# OBCv4_24.net
KiCad netlist of a schematic drawn in EAGLE
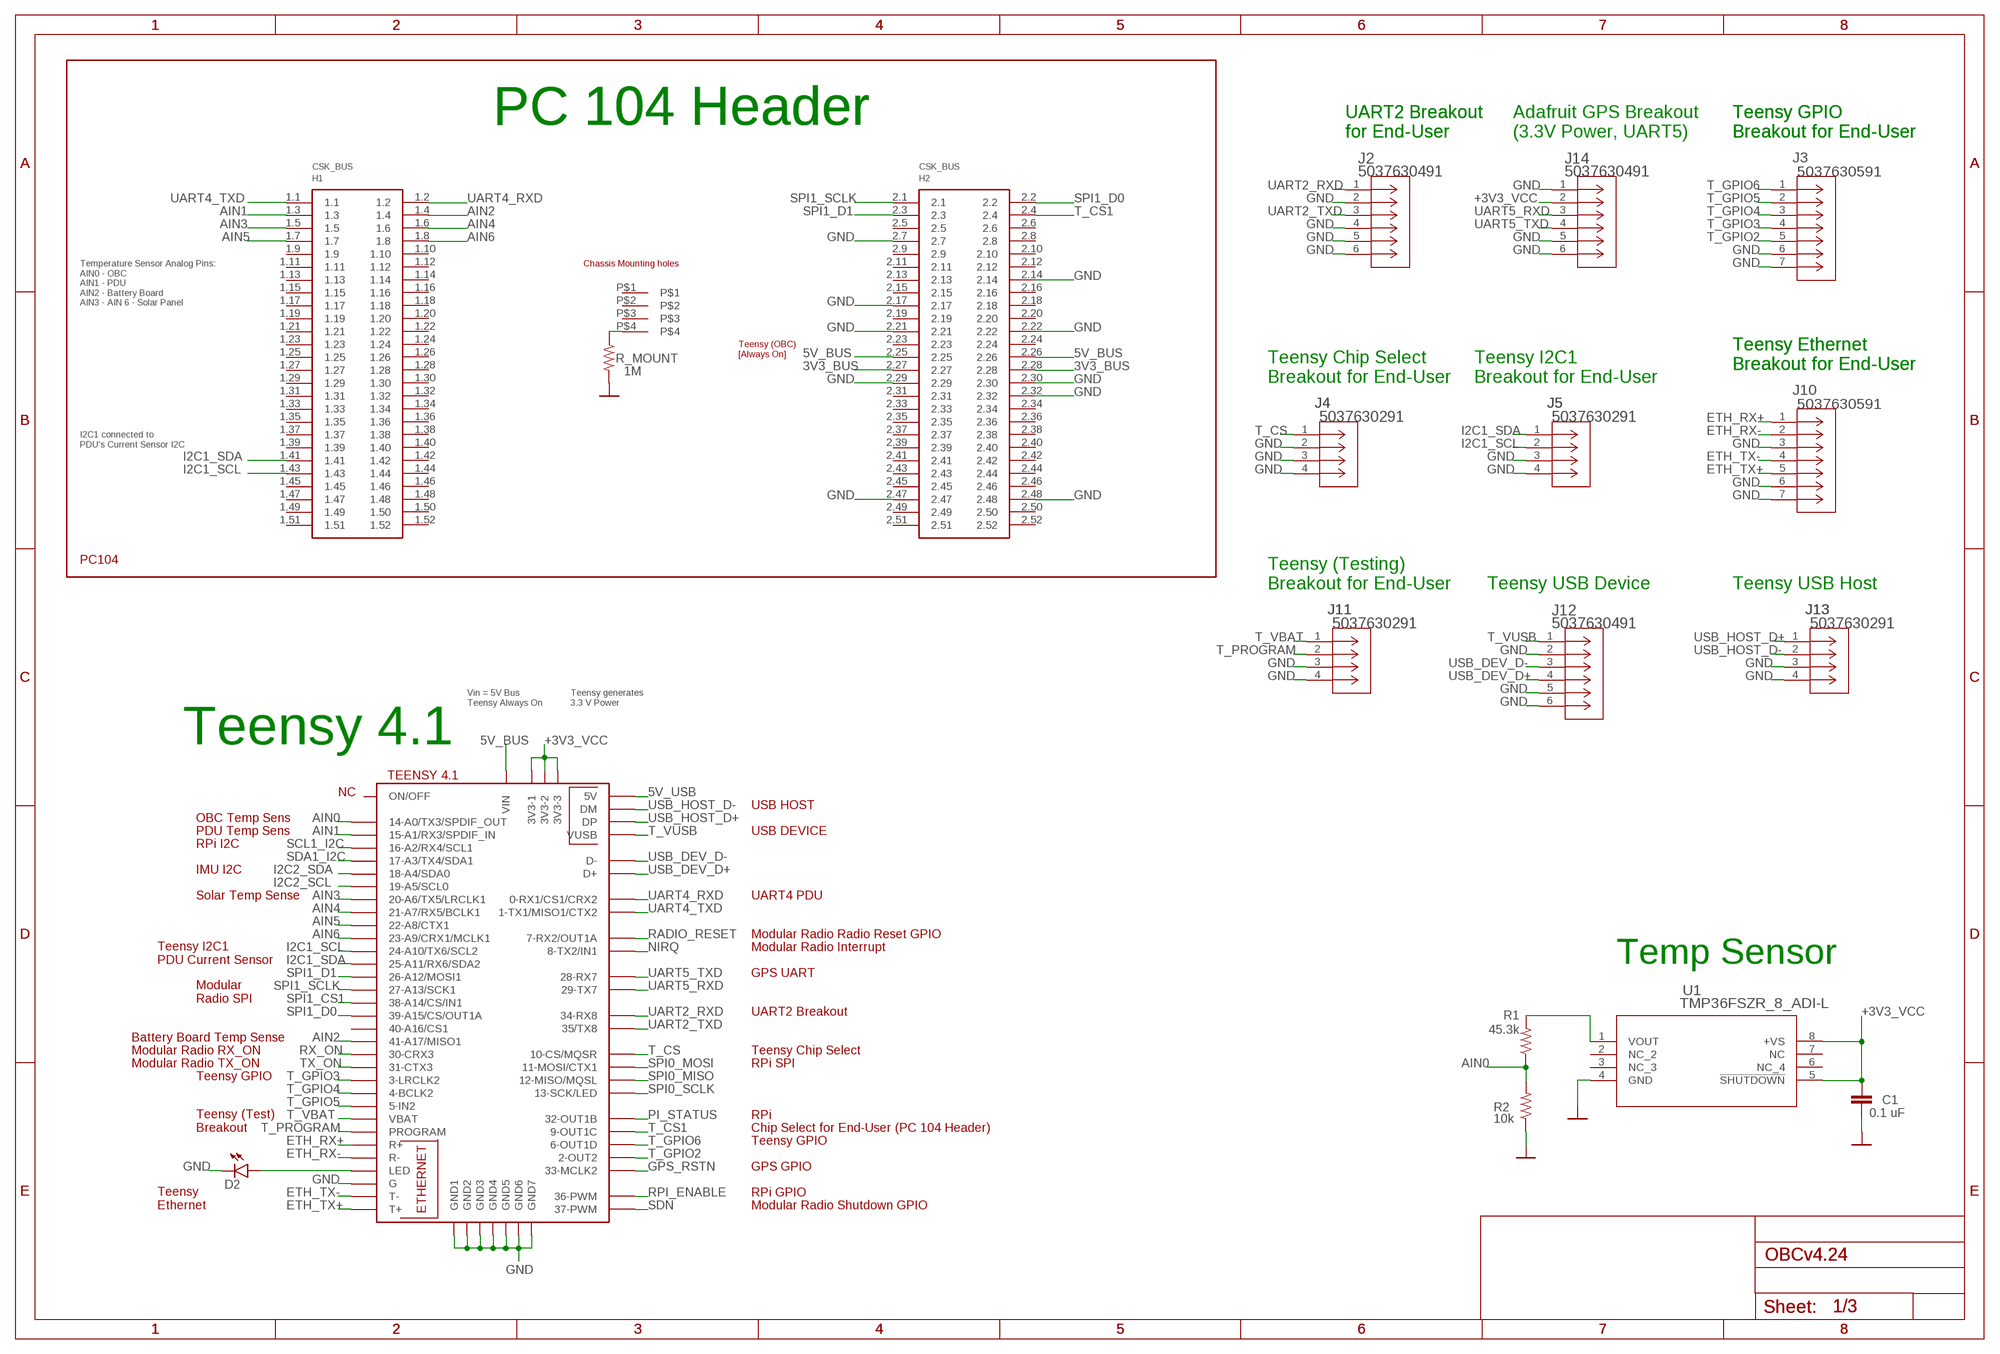
[diagram p0: schematic, sheet 1]
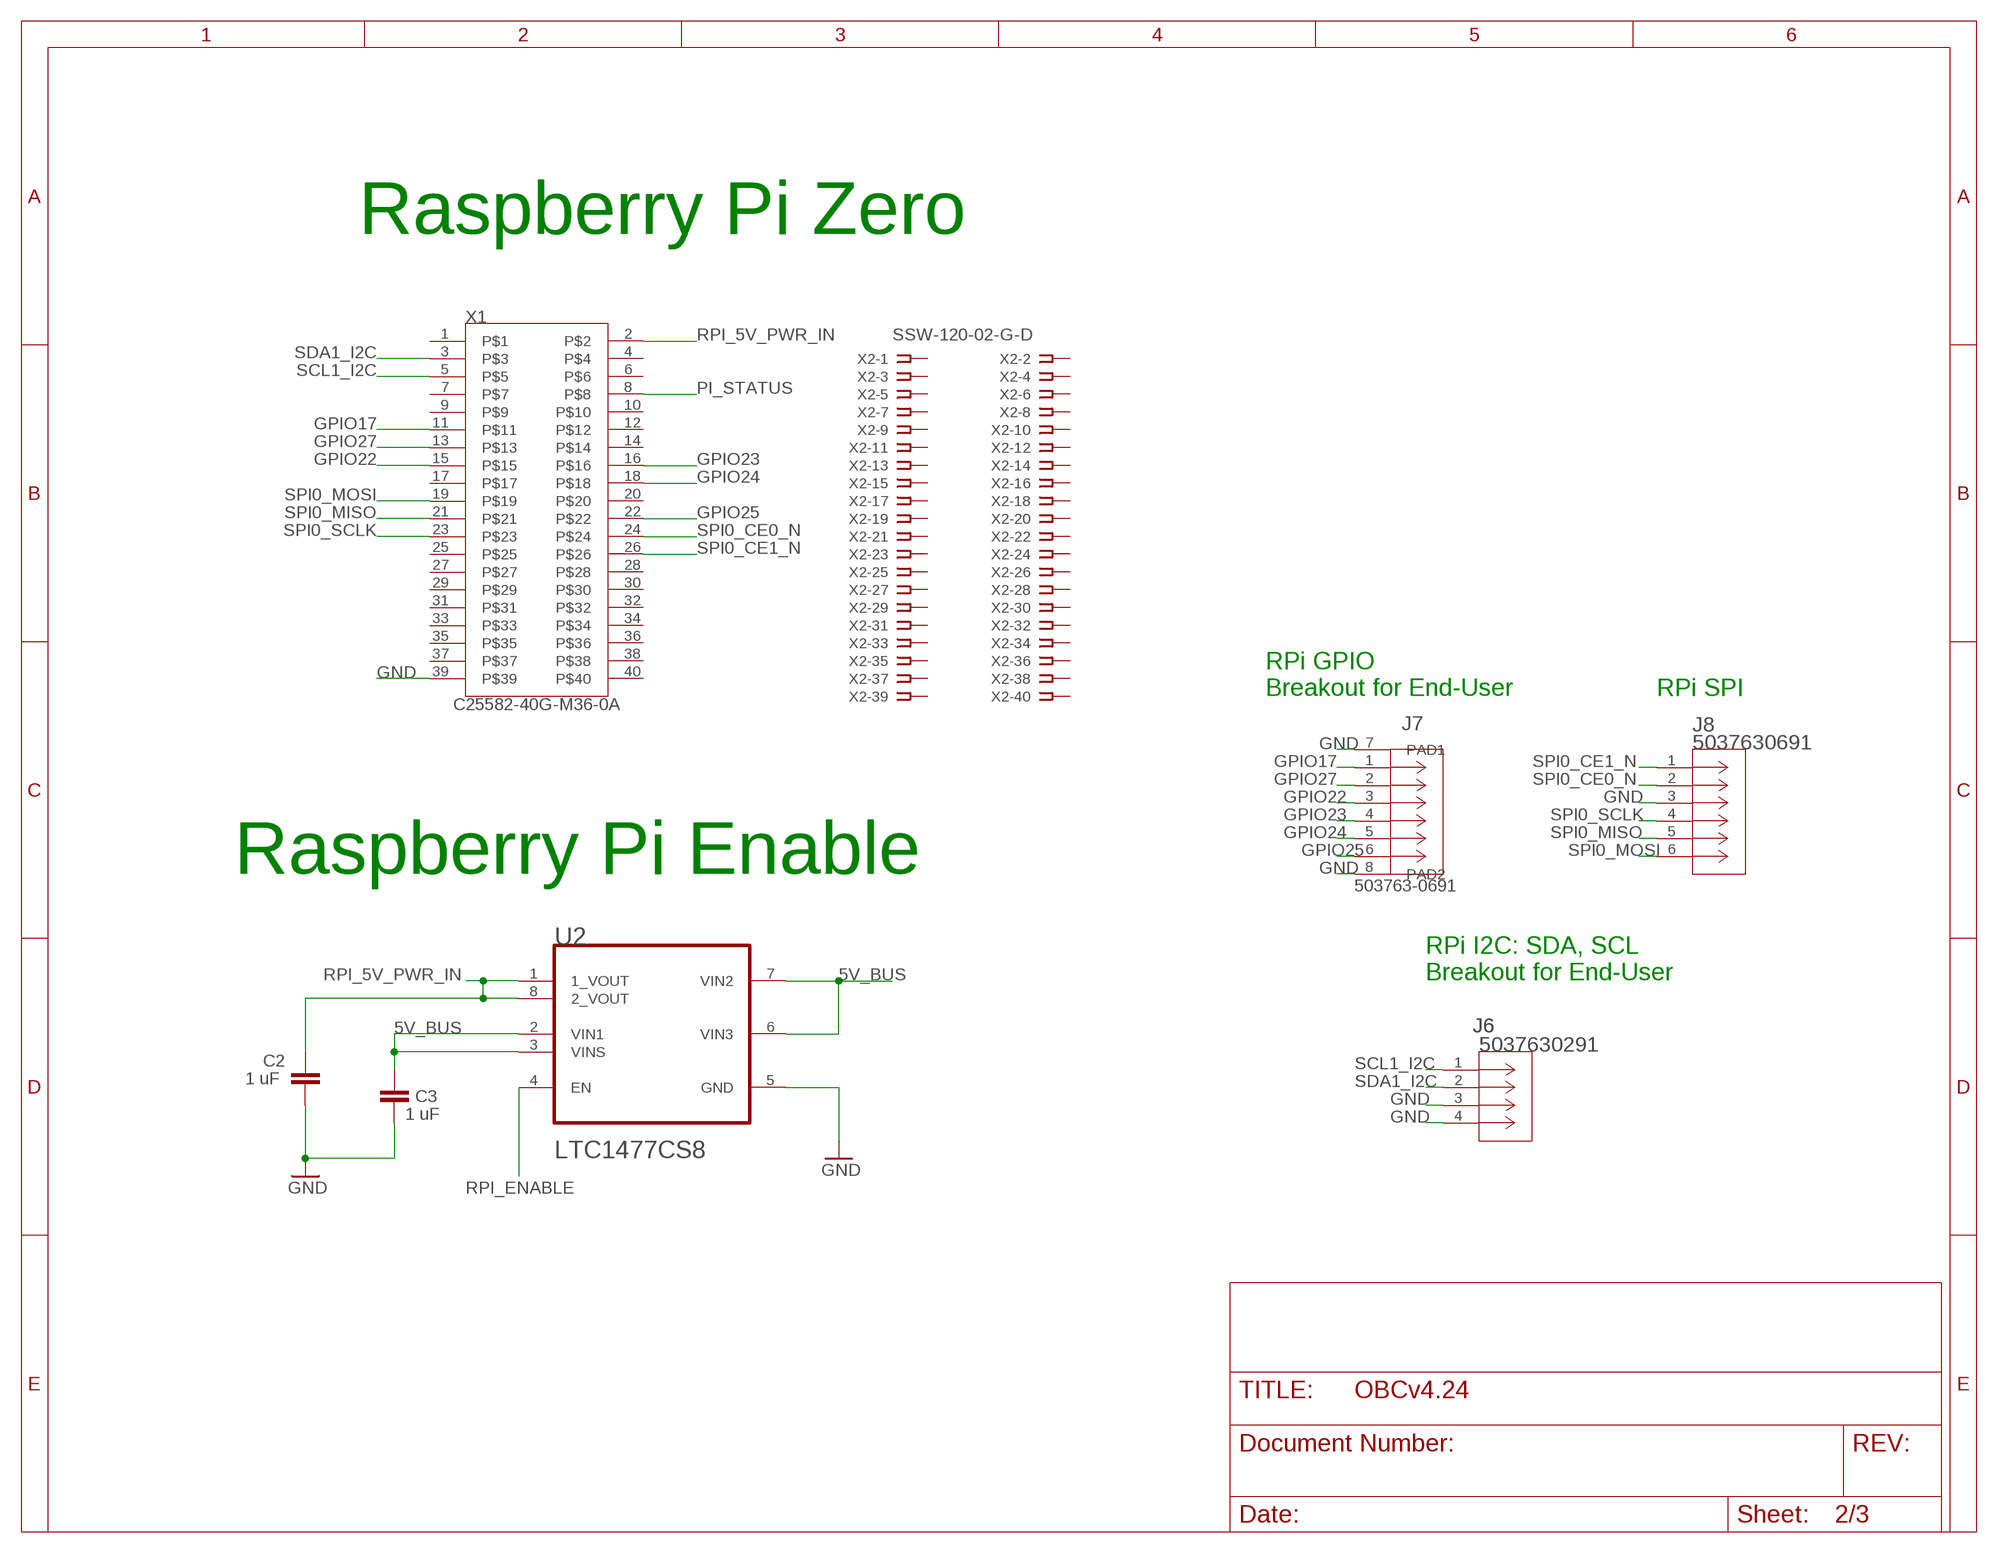
[diagram p1: schematic, sheet 2]
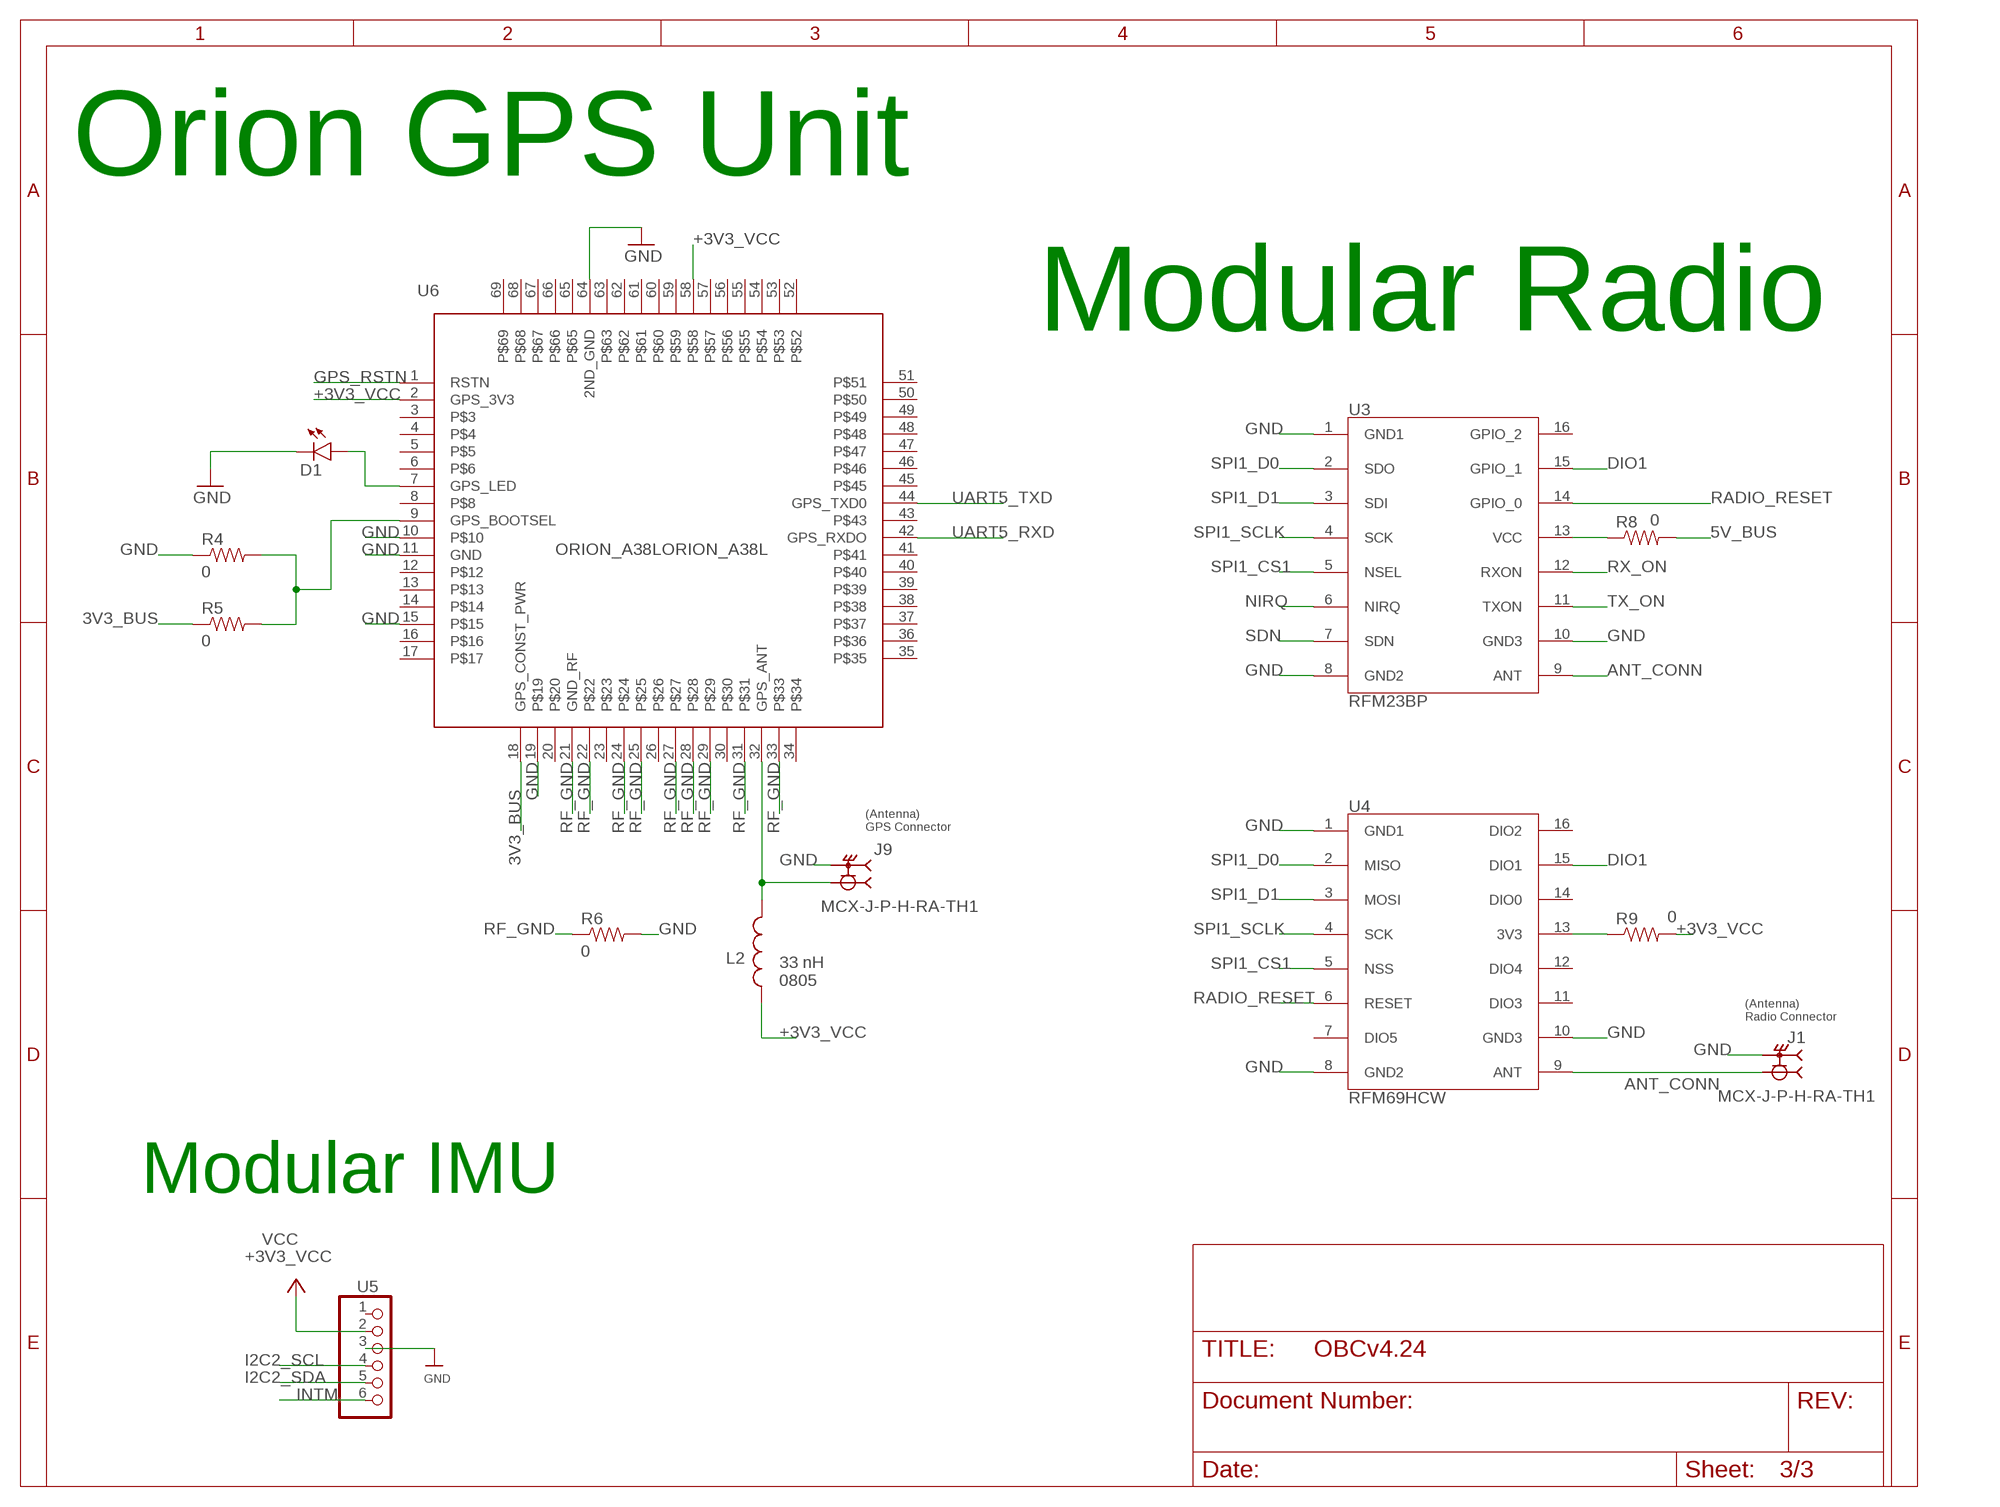
[diagram p2: schematic, sheet 3]

(export (version "E")
  (design (tool "Eeschema 10.0.6"))
  (components
    (comp (ref "D1")
      (value "LEDCHIP-LED0603")
      (footprint "eagle-import:CHIP-LED0603")
      (libsource (lib "eagle-import") (part "LEDCHIP-LED0603"))
    )
    (comp (ref "J1")
      (value "MCX-J-P-H-RA-TH1")
      (footprint "eagle-import:SAMTEC_MCX-J-P-H-RA-TH1")
      (fields (field (name "DIGI-KEY_PART_NUMBER") "SAM10607-ND") (field (name "MF") "Samtec"))
      (libsource (lib "eagle-import") (part "MCX-J-P-H-RA-TH1"))
    )
    (comp (ref "J9")
      (value "MCX-J-P-H-RA-TH1")
      (footprint "eagle-import:SAMTEC_MCX-J-P-H-RA-TH1")
      (fields (field (name "DIGI-KEY_PART_NUMBER") "SAM10607-ND") (field (name "MF") "Samtec"))
      (libsource (lib "eagle-import") (part "MCX-J-P-H-RA-TH1"))
    )
    (comp (ref "L2")
      (value "AIMC-0805-2N2S-T")
      (footprint "eagle-import:INDC2012X105N")
      (fields (field (name "DIGI-KEY_PART_NUMBER") "535-11562-1-ND") (field (name "MF") "Abracon"))
      (libsource (lib "eagle-import") (part "AIMC-0805-2N2S-T"))
    )
    (comp (ref "R4")
      (value "0")
      (footprint "eagle-import:0805")
      (libsource (lib "eagle-import") (part "RESISTOR0805-RES"))
    )
    (comp (ref "R5")
      (value "0")
      (footprint "eagle-import:0805")
      (libsource (lib "eagle-import") (part "RESISTOR0805-RES"))
    )
    (comp (ref "R6")
      (value "0")
      (footprint "eagle-import:0805")
      (libsource (lib "eagle-import") (part "RESISTOR0805-RES"))
    )
    (comp (ref "R8")
      (value "0")
      (footprint "eagle-import:R2512")
      (libsource (lib "eagle-import") (part "RESISTOR2512"))
    )
    (comp (ref "R9")
      (value "0")
      (footprint "eagle-import:R2512")
      (libsource (lib "eagle-import") (part "RESISTOR2512"))
    )
    (comp (ref "U3")
      (value "RFM23BP")
      (footprint "eagle-import:RFM23BP")
      (libsource (lib "eagle-import") (part "RFM23BP"))
    )
    (comp (ref "U4")
      (value "RFM69HCW")
      (footprint "eagle-import:RFM69HCW")
      (libsource (lib "eagle-import") (part "RFM69HCW"))
    )
    (comp (ref "U5")
      (value "HEADER-1X670MIL")
      (footprint "eagle-import:1X06_ROUND_70")
      (libsource (lib "eagle-import") (part "HEADER-1X670MIL"))
    )
    (comp (ref "U6")
      (value "ORION_A38LORION_A38L")
      (footprint "eagle-import:ORION_A38L")
      (libsource (lib "eagle-import") (part "ORION_A38LORION_A38L"))
    )
    (comp (ref "C1")
      (value "0.1 uF")
      (footprint "eagle-import:0805")
      (libsource (lib "eagle-import") (part "CAP0805"))
    )
    (comp (ref "D2")
      (value "LEDCHIP-LED0603")
      (footprint "eagle-import:CHIP-LED0603")
      (libsource (lib "eagle-import") (part "LEDCHIP-LED0603"))
    )
    (comp (ref "H1")
      (value "PC104_WCONN")
      (footprint "eagle-import:PC104_WCONN")
      (libsource (lib "eagle-import") (part "PC104_WCONN"))
    )
    (comp (ref "J2")
      (value "5037630491")
      (footprint "eagle-import:CON_5037630491")
      (fields (field (name "COPYRIGHT") "Copyright (C) 2018 Accelerated Designs. All rights reserved"))
      (libsource (lib "eagle-import") (part "5037630491"))
    )
    (comp (ref "J3")
      (value "5037630591")
      (footprint "eagle-import:CON_5037630591")
      (fields (field (name "COPYRIGHT") "Copyright (C) 2021 Ultra Librarian. All rights reserved."))
      (libsource (lib "eagle-import") (part "5037630591"))
    )
    (comp (ref "J4")
      (value "5037630291")
      (footprint "eagle-import:CON_5037630291")
      (fields (field (name "COPYRIGHT") "Copyright (C) 2018 Accelerated Designs. All rights reserved"))
      (libsource (lib "eagle-import") (part "5037630291"))
    )
    (comp (ref "J5")
      (value "5037630291")
      (footprint "eagle-import:CON_5037630291")
      (fields (field (name "COPYRIGHT") "Copyright (C) 2018 Accelerated Designs. All rights reserved"))
      (libsource (lib "eagle-import") (part "5037630291"))
    )
    (comp (ref "J10")
      (value "5037630591")
      (footprint "eagle-import:CON_5037630591")
      (fields (field (name "COPYRIGHT") "Copyright (C) 2021 Ultra Librarian. All rights reserved."))
      (libsource (lib "eagle-import") (part "5037630591"))
    )
    (comp (ref "J11")
      (value "5037630291")
      (footprint "eagle-import:CON_5037630291")
      (fields (field (name "COPYRIGHT") "Copyright (C) 2018 Accelerated Designs. All rights reserved"))
      (libsource (lib "eagle-import") (part "5037630291"))
    )
    (comp (ref "J12")
      (value "5037630491")
      (footprint "eagle-import:CON_5037630491")
      (fields (field (name "COPYRIGHT") "Copyright (C) 2018 Accelerated Designs. All rights reserved"))
      (libsource (lib "eagle-import") (part "5037630491"))
    )
    (comp (ref "J13")
      (value "5037630291")
      (footprint "eagle-import:CON_5037630291")
      (fields (field (name "COPYRIGHT") "Copyright (C) 2018 Accelerated Designs. All rights reserved"))
      (libsource (lib "eagle-import") (part "5037630291"))
    )
    (comp (ref "J14")
      (value "5037630491")
      (footprint "eagle-import:CON_5037630491")
      (fields (field (name "COPYRIGHT") "Copyright (C) 2018 Accelerated Designs. All rights reserved"))
      (libsource (lib "eagle-import") (part "5037630491"))
    )
    (comp (ref "R1")
      (value "45.3k")
      (footprint "eagle-import:0805")
      (libsource (lib "eagle-import") (part "RESISTOR0805-RES"))
    )
    (comp (ref "R2")
      (value "10k")
      (footprint "eagle-import:0805")
      (libsource (lib "eagle-import") (part "RESISTOR0805-RES"))
    )
    (comp (ref "R_MOUNT")
      (value "1M")
      (footprint "eagle-import:0805")
      (libsource (lib "eagle-import") (part "RESISTOR0805-RES"))
    )
    (comp (ref "U$1")
      (value "TEENSY41TEENSY")
      (footprint "eagle-import:TEENSY41")
      (libsource (lib "eagle-import") (part "TEENSY41TEENSY"))
    )
    (comp (ref "U1")
      (value "TMP36FSZR_8_ADI-L")
      (footprint "eagle-import:R_8_ADI-L")
      (fields
        (field (name "MANUFACTURER_PART_NUMBER") "TMP36FSZ")
        (field (name "COPYRIGHT") "Copyright (C) 2021 Ultra Librarian. All rights reserved.")
      )
      (libsource (lib "eagle-import") (part "TMP36FSZR_8_ADI-L"))
    )
    (comp (ref "C2")
      (value "1 uF")
      (footprint "eagle-import:0805")
      (libsource (lib "eagle-import") (part "CAP0805"))
    )
    (comp (ref "C3")
      (value "1 uF")
      (footprint "eagle-import:0805")
      (libsource (lib "eagle-import") (part "CAP0805"))
    )
    (comp (ref "J6")
      (value "5037630291")
      (footprint "eagle-import:CON_5037630291")
      (fields (field (name "COPYRIGHT") "Copyright (C) 2018 Accelerated Designs. All rights reserved"))
      (libsource (lib "eagle-import") (part "5037630291"))
    )
    (comp (ref "J7")
      (value "503763-0691")
      (footprint "eagle-import:CONN_503763-0691_MOL")
      (fields (field (name "COPYRIGHT") "Copyright (C) 2018 Accelerated Designs. All rights reserved"))
      (libsource (lib "eagle-import") (part "503763-0691"))
    )
    (comp (ref "J8")
      (value "5037630691")
      (footprint "eagle-import:CONN_503763-0691_MOL")
      (fields
        (field (name "MANUFACTURER_PART_NUMBER") "503763-0691")
        (field (name "COPYRIGHT") "Copyright (C) 2018 Accelerated Designs. All rights reserved")
      )
      (libsource (lib "eagle-import") (part "5037630691"))
    )
    (comp (ref "U2")
      (value "LTC1477CS8LINEAR_TECHNOLOGY_LTC1477CS8_0_2")
      (footprint "eagle-import:LINEAR_TECHNOLOGY_LTC1477CS8_2")
      (fields (field (name "MF") "Linear Technology") (field (name "MPN") "LTC1477CS8"))
      (libsource (lib "eagle-import") (part "LTC1477CS8LINEAR_TECHNOLOGY_LTC1477CS8_0_2"))
    )
    (comp (ref "X1")
      (value "C25582-40G-M36-0A")
      (footprint "eagle-import:ADAFRUIT_C25582-40G-M36-0A_0")
      (libsource (lib "eagle-import") (part "C25582-40G-M36-0A"))
    )
    (comp (ref "X2")
      (value "SSW-120-02-G-D")
      (footprint "eagle-import:SSW-120-02-G-D")
      (fields (field (name "MF") "Samtec Inc."))
      (libsource (lib "eagle-import") (part "SSW-120-02-G-D"))
    )
  )
  (nets
    (net (code "1") (name "+3V3_VCC") (class "Default")
      (node (ref "C1") (pin "1") (pinfunction "1_1") (pintype "passive"))
      (node (ref "J14") (pin "2") (pinfunction "2_2") (pintype "passive"))
      (node (ref "L2") (pin "1") (pinfunction "1_1") (pintype "passive"))
      (node (ref "R9") (pin "2") (pinfunction "2_2") (pintype "passive"))
      (node (ref "U$1") (pin "3V3-1") (pinfunction "3V3-1_3V3-1") (pintype "bidirectional"))
      (node (ref "U$1") (pin "3V3-2") (pinfunction "3V3-2_3V3-2") (pintype "bidirectional"))
      (node (ref "U$1") (pin "3V3-3") (pinfunction "3V3-3_3V3-3") (pintype "bidirectional"))
      (node (ref "U1") (pin "5") (pinfunction "~{SHUTDOWN}_5") (pintype "passive"))
      (node (ref "U1") (pin "8") (pinfunction "+VS_8") (pintype "power_in"))
      (node (ref "U5") (pin "2") (pinfunction "2_2") (pintype "passive"))
      (node (ref "U6") (pin "2") (pinfunction "GPS_3V3_2") (pintype "bidirectional"))
      (node (ref "U6") (pin "58") (pinfunction "P$58_58") (pintype "bidirectional"))
    )
    (net (code "2") (name "3V3_BUS") (class "Default")
      (node (ref "H1") (pin "2.27") (pinfunction "2.27_2.27") (pintype "bidirectional"))
      (node (ref "H1") (pin "2.28") (pinfunction "2.28_2.28") (pintype "bidirectional"))
      (node (ref "R5") (pin "1") (pinfunction "1_1") (pintype "passive"))
      (node (ref "U6") (pin "18") (pinfunction "GPS_CONST_PWR_18") (pintype "bidirectional"))
    )
    (net (code "3") (name "5V_BUS") (class "Default")
      (node (ref "C3") (pin "1") (pinfunction "1_1") (pintype "passive"))
      (node (ref "H1") (pin "2.25") (pinfunction "2.25_2.25") (pintype "bidirectional"))
      (node (ref "H1") (pin "2.26") (pinfunction "2.26_2.26") (pintype "bidirectional"))
      (node (ref "R8") (pin "2") (pinfunction "2_2") (pintype "passive"))
      (node (ref "U$1") (pin "VIN") (pinfunction "VIN_VIN") (pintype "bidirectional"))
      (node (ref "U2") (pin "2") (pinfunction "VIN1_2") (pintype "power_in"))
      (node (ref "U2") (pin "3") (pinfunction "VINS_3") (pintype "power_in"))
      (node (ref "U2") (pin "6") (pinfunction "VIN3_6") (pintype "power_in"))
      (node (ref "U2") (pin "7") (pinfunction "VIN2_7") (pintype "power_in"))
    )
    (net (code "4") (name "5V_USB") (class "Default")
      (node (ref "U$1") (pin "+5V") (pinfunction "5V_+5V") (pintype "bidirectional"))
    )
    (net (code "5") (name "AIN0") (class "Default")
      (node (ref "R1") (pin "1") (pinfunction "1_1") (pintype "passive"))
      (node (ref "R2") (pin "2") (pinfunction "2_2") (pintype "passive"))
      (node (ref "U$1") (pin "14-A0/TX3/SPDIF_OUT") (pinfunction "14-A0/TX3/SPDIF_OUT_14-A0/TX3/SPDIF_OUT") (pintype "bidirectional"))
    )
    (net (code "6") (name "AIN1") (class "Default")
      (node (ref "H1") (pin "1.3") (pinfunction "1.3_1.3") (pintype "bidirectional"))
      (node (ref "U$1") (pin "15-A1/RX3/SPDIF_IN") (pinfunction "15-A1/RX3/SPDIF_IN_15-A1/RX3/SPDIF_IN") (pintype "bidirectional"))
    )
    (net (code "7") (name "AIN2") (class "Default")
      (node (ref "H1") (pin "1.4") (pinfunction "1.4_1.4") (pintype "bidirectional"))
      (node (ref "U$1") (pin "41-A17/MISO1") (pinfunction "41-A17/MISO1_41-A17/MISO1") (pintype "bidirectional"))
    )
    (net (code "8") (name "AIN3") (class "Default")
      (node (ref "H1") (pin "1.5") (pinfunction "1.5_1.5") (pintype "bidirectional"))
      (node (ref "U$1") (pin "20-A6/TX5/LRCLK1") (pinfunction "20-A6/TX5/LRCLK1_20-A6/TX5/LRCLK1") (pintype "bidirectional"))
    )
    (net (code "9") (name "AIN4") (class "Default")
      (node (ref "H1") (pin "1.6") (pinfunction "1.6_1.6") (pintype "bidirectional"))
      (node (ref "U$1") (pin "21-A7/RX5/BCLK1") (pinfunction "21-A7/RX5/BCLK1_21-A7/RX5/BCLK1") (pintype "bidirectional"))
    )
    (net (code "10") (name "AIN5") (class "Default")
      (node (ref "H1") (pin "1.7") (pinfunction "1.7_1.7") (pintype "bidirectional"))
      (node (ref "U$1") (pin "22-A8/CTX1") (pinfunction "22-A8/CTX1_22-A8/CTX1") (pintype "bidirectional"))
    )
    (net (code "11") (name "AIN6") (class "Default")
      (node (ref "H1") (pin "1.8") (pinfunction "1.8_1.8") (pintype "bidirectional"))
      (node (ref "U$1") (pin "23-A9/CRX1/MCLK1") (pinfunction "23-A9/CRX1/MCLK1_23-A9/CRX1/MCLK1") (pintype "bidirectional"))
    )
    (net (code "12") (name "ANT_CONN") (class "Default")
      (node (ref "J1") (pin "1") (pinfunction "1_1") (pintype "passive"))
      (node (ref "U3") (pin "9") (pinfunction "ANT_9") (pintype "bidirectional"))
      (node (ref "U4") (pin "9") (pinfunction "ANT_9") (pintype "bidirectional"))
    )
    (net (code "13") (name "DIO1") (class "Default")
      (node (ref "U3") (pin "15") (pinfunction "GPIO_1_15") (pintype "bidirectional"))
      (node (ref "U4") (pin "15") (pinfunction "DIO1_15") (pintype "bidirectional"))
    )
    (net (code "14") (name "ETH_RX+") (class "Default")
      (node (ref "J10") (pin "1") (pinfunction "1_1") (pintype "passive"))
      (node (ref "U$1") (pin "R+") (pinfunction "R+_R+") (pintype "bidirectional"))
    )
    (net (code "15") (name "ETH_RX-") (class "Default")
      (node (ref "J10") (pin "2") (pinfunction "2_2") (pintype "passive"))
      (node (ref "U$1") (pin "R-") (pinfunction "R-_R-") (pintype "bidirectional"))
    )
    (net (code "16") (name "ETH_TX+") (class "Default")
      (node (ref "J10") (pin "5") (pinfunction "5_5") (pintype "passive"))
      (node (ref "U$1") (pin "T+") (pinfunction "T+_T+") (pintype "bidirectional"))
    )
    (net (code "17") (name "ETH_TX-") (class "Default")
      (node (ref "J10") (pin "4") (pinfunction "4_4") (pintype "passive"))
      (node (ref "U$1") (pin "T-") (pinfunction "T-_T-") (pintype "bidirectional"))
    )
    (net (code "18") (name "GND") (class "Default")
      (node (ref "C1") (pin "2") (pinfunction "2_2") (pintype "passive"))
      (node (ref "C2") (pin "2") (pinfunction "2_2") (pintype "passive"))
      (node (ref "C3") (pin "2") (pinfunction "2_2") (pintype "passive"))
      (node (ref "D1") (pin "C") (pinfunction "C_C") (pintype "passive"))
      (node (ref "D2") (pin "C") (pinfunction "C_C") (pintype "passive"))
      (node (ref "H1") (pin "2.14") (pinfunction "2.14_2.14") (pintype "bidirectional"))
      (node (ref "H1") (pin "2.17") (pinfunction "2.17_2.17") (pintype "bidirectional"))
      (node (ref "H1") (pin "2.21") (pinfunction "2.21_2.21") (pintype "bidirectional"))
      (node (ref "H1") (pin "2.22") (pinfunction "2.22_2.22") (pintype "bidirectional"))
      (node (ref "H1") (pin "2.29") (pinfunction "2.29_2.29") (pintype "bidirectional"))
      (node (ref "H1") (pin "2.30") (pinfunction "2.30_2.30") (pintype "bidirectional"))
      (node (ref "H1") (pin "2.32") (pinfunction "2.32_2.32") (pintype "bidirectional"))
      (node (ref "H1") (pin "2.47") (pinfunction "2.47_2.47") (pintype "bidirectional"))
      (node (ref "H1") (pin "2.48") (pinfunction "2.48_2.48") (pintype "bidirectional"))
      (node (ref "H1") (pin "2.7") (pinfunction "2.7_2.7") (pintype "bidirectional"))
      (node (ref "J1") (pin "S1") (pinfunction "2_S1") (pintype "passive"))
      (node (ref "J1") (pin "S2") (pinfunction "2_S2") (pintype "passive"))
      (node (ref "J1") (pin "S3") (pinfunction "2_S3") (pintype "passive"))
      (node (ref "J1") (pin "S4") (pinfunction "2_S4") (pintype "passive"))
      (node (ref "J10") (pin "3") (pinfunction "3_3") (pintype "passive"))
      (node (ref "J10") (pin "6") (pinfunction "6_6") (pintype "passive"))
      (node (ref "J10") (pin "7") (pinfunction "7_7") (pintype "passive"))
      (node (ref "J11") (pin "3") (pinfunction "3_3") (pintype "passive"))
      (node (ref "J11") (pin "4") (pinfunction "4_4") (pintype "passive"))
      (node (ref "J12") (pin "2") (pinfunction "2_2") (pintype "passive"))
      (node (ref "J12") (pin "5") (pinfunction "5_5") (pintype "passive"))
      (node (ref "J12") (pin "6") (pinfunction "6_6") (pintype "passive"))
      (node (ref "J13") (pin "3") (pinfunction "3_3") (pintype "passive"))
      (node (ref "J13") (pin "4") (pinfunction "4_4") (pintype "passive"))
      (node (ref "J14") (pin "1") (pinfunction "1_1") (pintype "passive"))
      (node (ref "J14") (pin "5") (pinfunction "5_5") (pintype "passive"))
      (node (ref "J14") (pin "6") (pinfunction "6_6") (pintype "passive"))
      (node (ref "J2") (pin "2") (pinfunction "2_2") (pintype "passive"))
      (node (ref "J2") (pin "4") (pinfunction "4_4") (pintype "passive"))
      (node (ref "J2") (pin "5") (pinfunction "5_5") (pintype "passive"))
      (node (ref "J2") (pin "6") (pinfunction "6_6") (pintype "passive"))
      (node (ref "J3") (pin "6") (pinfunction "6_6") (pintype "passive"))
      (node (ref "J3") (pin "7") (pinfunction "7_7") (pintype "passive"))
      (node (ref "J4") (pin "2") (pinfunction "2_2") (pintype "passive"))
      (node (ref "J4") (pin "3") (pinfunction "3_3") (pintype "passive"))
      (node (ref "J4") (pin "4") (pinfunction "4_4") (pintype "passive"))
      (node (ref "J5") (pin "3") (pinfunction "3_3") (pintype "passive"))
      (node (ref "J5") (pin "4") (pinfunction "4_4") (pintype "passive"))
      (node (ref "J6") (pin "3") (pinfunction "3_3") (pintype "passive"))
      (node (ref "J6") (pin "4") (pinfunction "4_4") (pintype "passive"))
      (node (ref "J7") (pin "7") (pinfunction "PAD1_7") (pintype "bidirectional"))
      (node (ref "J7") (pin "8") (pinfunction "PAD2_8") (pintype "bidirectional"))
      (node (ref "J8") (pin "3") (pinfunction "3_3") (pintype "passive"))
      (node (ref "J9") (pin "S1") (pinfunction "2_S1") (pintype "passive"))
      (node (ref "J9") (pin "S2") (pinfunction "2_S2") (pintype "passive"))
      (node (ref "J9") (pin "S3") (pinfunction "2_S3") (pintype "passive"))
      (node (ref "J9") (pin "S4") (pinfunction "2_S4") (pintype "passive"))
      (node (ref "R2") (pin "1") (pinfunction "1_1") (pintype "passive"))
      (node (ref "R4") (pin "1") (pinfunction "1_1") (pintype "passive"))
      (node (ref "R6") (pin "2") (pinfunction "2_2") (pintype "passive"))
      (node (ref "R_MOUNT") (pin "2") (pinfunction "2_2") (pintype "passive"))
      (node (ref "U$1") (pin "G") (pinfunction "G_G") (pintype "bidirectional"))
      (node (ref "U$1") (pin "GND") (pinfunction "GND7_GND") (pintype "bidirectional"))
      (node (ref "U$1") (pin "GND1") (pinfunction "GND1_GND1") (pintype "bidirectional"))
      (node (ref "U$1") (pin "GND2") (pinfunction "GND2_GND2") (pintype "bidirectional"))
      (node (ref "U$1") (pin "GND3") (pinfunction "GND3_GND3") (pintype "bidirectional"))
      (node (ref "U$1") (pin "GND4") (pinfunction "GND4_GND4") (pintype "bidirectional"))
      (node (ref "U$1") (pin "GND5") (pinfunction "GND5_GND5") (pintype "bidirectional"))
      (node (ref "U$1") (pin "GND6") (pinfunction "GND6_GND6") (pintype "bidirectional"))
      (node (ref "U1") (pin "4") (pinfunction "GND_4") (pintype "passive"))
      (node (ref "U2") (pin "5") (pinfunction "GND_5") (pintype "power_in"))
      (node (ref "U3") (pin "1") (pinfunction "GND1_1") (pintype "bidirectional"))
      (node (ref "U3") (pin "10") (pinfunction "GND3_10") (pintype "bidirectional"))
      (node (ref "U3") (pin "8") (pinfunction "GND2_8") (pintype "bidirectional"))
      (node (ref "U4") (pin "1") (pinfunction "GND1_1") (pintype "bidirectional"))
      (node (ref "U4") (pin "10") (pinfunction "GND3_10") (pintype "bidirectional"))
      (node (ref "U4") (pin "8") (pinfunction "GND2_8") (pintype "bidirectional"))
      (node (ref "U5") (pin "3") (pinfunction "3_3") (pintype "passive"))
      (node (ref "U6") (pin "10") (pinfunction "P$10_10") (pintype "bidirectional"))
      (node (ref "U6") (pin "11") (pinfunction "GND_11") (pintype "bidirectional"))
      (node (ref "U6") (pin "15") (pinfunction "P$15_15") (pintype "bidirectional"))
      (node (ref "U6") (pin "19") (pinfunction "P$19_19") (pintype "bidirectional"))
      (node (ref "U6") (pin "64") (pinfunction "2ND_GND_64") (pintype "bidirectional"))
      (node (ref "X1") (pin "39") (pinfunction "P$39_39") (pintype "bidirectional"))
    )
    (net (code "19") (name "GPIO17") (class "Default")
      (node (ref "J7") (pin "1") (pinfunction "1_1") (pintype "passive"))
      (node (ref "X1") (pin "11") (pinfunction "P$11_11") (pintype "bidirectional"))
    )
    (net (code "20") (name "GPIO22") (class "Default")
      (node (ref "J7") (pin "3") (pinfunction "3_3") (pintype "passive"))
      (node (ref "X1") (pin "15") (pinfunction "P$15_15") (pintype "bidirectional"))
    )
    (net (code "21") (name "GPIO23") (class "Default")
      (node (ref "J7") (pin "4") (pinfunction "4_4") (pintype "passive"))
      (node (ref "X1") (pin "16") (pinfunction "P$16_16") (pintype "bidirectional"))
    )
    (net (code "22") (name "GPIO24") (class "Default")
      (node (ref "J7") (pin "5") (pinfunction "5_5") (pintype "passive"))
      (node (ref "X1") (pin "18") (pinfunction "P$18_18") (pintype "bidirectional"))
    )
    (net (code "23") (name "GPIO25") (class "Default")
      (node (ref "J7") (pin "6") (pinfunction "6_6") (pintype "passive"))
      (node (ref "X1") (pin "22") (pinfunction "P$22_22") (pintype "bidirectional"))
    )
    (net (code "24") (name "GPIO27") (class "Default")
      (node (ref "J7") (pin "2") (pinfunction "2_2") (pintype "passive"))
      (node (ref "X1") (pin "13") (pinfunction "P$13_13") (pintype "bidirectional"))
    )
    (net (code "25") (name "GPS_RSTN") (class "Default")
      (node (ref "U$1") (pin "33-MCLK2") (pinfunction "33-MCLK2_33-MCLK2") (pintype "bidirectional"))
      (node (ref "U6") (pin "1") (pinfunction "RSTN_1") (pintype "bidirectional"))
    )
    (net (code "26") (name "I2C1_SCL") (class "Default")
      (node (ref "H1") (pin "1.43") (pinfunction "1.43_1.43") (pintype "bidirectional"))
      (node (ref "J5") (pin "2") (pinfunction "2_2") (pintype "passive"))
      (node (ref "U$1") (pin "24-A10/TX6/SCL2") (pinfunction "24-A10/TX6/SCL2_24-A10/TX6/SCL2") (pintype "bidirectional"))
    )
    (net (code "27") (name "I2C1_SDA") (class "Default")
      (node (ref "H1") (pin "1.41") (pinfunction "1.41_1.41") (pintype "bidirectional"))
      (node (ref "J5") (pin "1") (pinfunction "1_1") (pintype "passive"))
      (node (ref "U$1") (pin "25-A11/RX6/SDA2") (pinfunction "25-A11/RX6/SDA2_25-A11/RX6/SDA2") (pintype "bidirectional"))
    )
    (net (code "28") (name "I2C2_SCL") (class "Default")
      (node (ref "U$1") (pin "19-A5/SCL0") (pinfunction "19-A5/SCL0_19-A5/SCL0") (pintype "bidirectional"))
      (node (ref "U5") (pin "4") (pinfunction "4_4") (pintype "passive"))
    )
    (net (code "29") (name "I2C2_SDA") (class "Default")
      (node (ref "U$1") (pin "18-A4/SDA0") (pinfunction "18-A4/SDA0_18-A4/SDA0") (pintype "bidirectional"))
      (node (ref "U5") (pin "5") (pinfunction "5_5") (pintype "passive"))
    )
    (net (code "30") (name "INTM") (class "Default")
      (node (ref "U5") (pin "6") (pinfunction "6_6") (pintype "passive"))
    )
    (net (code "31") (name "NIRQ") (class "Default")
      (node (ref "U$1") (pin "8-TX2/IN1") (pinfunction "8-TX2/IN1_8-TX2/IN1") (pintype "bidirectional"))
      (node (ref "U3") (pin "6") (pinfunction "NIRQ_6") (pintype "bidirectional"))
    )
    (net (code "32") (name "Net-(D2-PadA)") (class "Default")
      (node (ref "D2") (pin "A") (pinfunction "A_A") (pintype "passive"))
      (node (ref "U$1") (pin "LED") (pinfunction "LED_LED") (pintype "bidirectional"))
    )
    (net (code "33") (name "Net-(H1-PadP$4)") (class "Default")
      (node (ref "H1") (pin "P$4") (pinfunction "P$4_P$4") (pintype "bidirectional"))
      (node (ref "R_MOUNT") (pin "1") (pinfunction "1_1") (pintype "passive"))
    )
    (net (code "34") (name "Net-(U1-VOUT)") (class "Default")
      (node (ref "R1") (pin "2") (pinfunction "2_2") (pintype "passive"))
      (node (ref "U1") (pin "1") (pinfunction "VOUT_1") (pintype "output"))
    )
    (net (code "35") (name "Net-(U3-VCC)") (class "Default")
      (node (ref "R8") (pin "1") (pinfunction "1_1") (pintype "passive"))
      (node (ref "U3") (pin "13") (pinfunction "VCC_13") (pintype "bidirectional"))
    )
    (net (code "36") (name "Net-(U4-3V3)") (class "Default")
      (node (ref "R9") (pin "1") (pinfunction "1_1") (pintype "passive"))
      (node (ref "U4") (pin "13") (pinfunction "3V3_13") (pintype "bidirectional"))
    )
    (net (code "37") (name "Net-(U6-GPS_ANT)") (class "Default")
      (node (ref "J9") (pin "1") (pinfunction "1_1") (pintype "passive"))
      (node (ref "L2") (pin "2") (pinfunction "2_2") (pintype "passive"))
      (node (ref "U6") (pin "32") (pinfunction "GPS_ANT_32") (pintype "bidirectional"))
    )
    (net (code "38") (name "Net-(U6-GPS_BOOTSEL)") (class "Default")
      (node (ref "R4") (pin "2") (pinfunction "2_2") (pintype "passive"))
      (node (ref "R5") (pin "2") (pinfunction "2_2") (pintype "passive"))
      (node (ref "U6") (pin "9") (pinfunction "GPS_BOOTSEL_9") (pintype "bidirectional"))
    )
    (net (code "39") (name "Net-(U6-GPS_LED)") (class "Default")
      (node (ref "D1") (pin "A") (pinfunction "A_A") (pintype "passive"))
      (node (ref "U6") (pin "7") (pinfunction "GPS_LED_7") (pintype "bidirectional"))
    )
    (net (code "40") (name "PI_STATUS") (class "Default")
      (node (ref "U$1") (pin "32-OUT1B") (pinfunction "32-OUT1B_32-OUT1B") (pintype "bidirectional"))
      (node (ref "X1") (pin "8") (pinfunction "P$8_8") (pintype "bidirectional"))
    )
    (net (code "41") (name "RADIO_RESET") (class "Default")
      (node (ref "U$1") (pin "7-RX2/OUT1A") (pinfunction "7-RX2/OUT1A_7-RX2/OUT1A") (pintype "bidirectional"))
      (node (ref "U3") (pin "14") (pinfunction "GPIO_0_14") (pintype "bidirectional"))
      (node (ref "U4") (pin "6") (pinfunction "RESET_6") (pintype "bidirectional"))
    )
    (net (code "42") (name "RF_GND") (class "Default")
      (node (ref "R6") (pin "1") (pinfunction "1_1") (pintype "passive"))
      (node (ref "U6") (pin "21") (pinfunction "GND_RF_21") (pintype "bidirectional"))
      (node (ref "U6") (pin "22") (pinfunction "P$22_22") (pintype "bidirectional"))
      (node (ref "U6") (pin "24") (pinfunction "P$24_24") (pintype "bidirectional"))
      (node (ref "U6") (pin "25") (pinfunction "P$25_25") (pintype "bidirectional"))
      (node (ref "U6") (pin "27") (pinfunction "P$27_27") (pintype "bidirectional"))
      (node (ref "U6") (pin "28") (pinfunction "P$28_28") (pintype "bidirectional"))
      (node (ref "U6") (pin "29") (pinfunction "P$29_29") (pintype "bidirectional"))
      (node (ref "U6") (pin "31") (pinfunction "P$31_31") (pintype "bidirectional"))
      (node (ref "U6") (pin "33") (pinfunction "P$33_33") (pintype "bidirectional"))
    )
    (net (code "43") (name "RPI_5V_PWR_IN") (class "Default")
      (node (ref "C2") (pin "1") (pinfunction "1_1") (pintype "passive"))
      (node (ref "U2") (pin "1") (pinfunction "1_VOUT_1") (pintype "power_in"))
      (node (ref "U2") (pin "8") (pinfunction "2_VOUT_8") (pintype "power_in"))
      (node (ref "X1") (pin "2") (pinfunction "P$2_2") (pintype "bidirectional"))
    )
    (net (code "44") (name "RPI_ENABLE") (class "Default")
      (node (ref "U$1") (pin "36-PWM") (pinfunction "36-PWM_36-PWM") (pintype "bidirectional"))
      (node (ref "U2") (pin "4") (pinfunction "EN_4") (pintype "input"))
    )
    (net (code "45") (name "RX_ON") (class "Default")
      (node (ref "U$1") (pin "30-CRX3") (pinfunction "30-CRX3_30-CRX3") (pintype "bidirectional"))
      (node (ref "U3") (pin "12") (pinfunction "RXON_12") (pintype "bidirectional"))
    )
    (net (code "46") (name "SCL1_I2C") (class "Default")
      (node (ref "J6") (pin "1") (pinfunction "1_1") (pintype "passive"))
      (node (ref "U$1") (pin "16-A2/RX4/SCL1") (pinfunction "16-A2/RX4/SCL1_16-A2/RX4/SCL1") (pintype "bidirectional"))
      (node (ref "X1") (pin "5") (pinfunction "P$5_5") (pintype "bidirectional"))
    )
    (net (code "47") (name "SDA1_I2C") (class "Default")
      (node (ref "J6") (pin "2") (pinfunction "2_2") (pintype "passive"))
      (node (ref "U$1") (pin "17-A3/TX4/SDA1") (pinfunction "17-A3/TX4/SDA1_17-A3/TX4/SDA1") (pintype "bidirectional"))
      (node (ref "X1") (pin "3") (pinfunction "P$3_3") (pintype "bidirectional"))
    )
    (net (code "48") (name "SDN") (class "Default")
      (node (ref "U$1") (pin "37-PWM") (pinfunction "37-PWM_37-PWM") (pintype "bidirectional"))
      (node (ref "U3") (pin "7") (pinfunction "SDN_7") (pintype "bidirectional"))
    )
    (net (code "49") (name "SPI0_CE0_N") (class "Default")
      (node (ref "J8") (pin "2") (pinfunction "2_2") (pintype "passive"))
      (node (ref "X1") (pin "24") (pinfunction "P$24_24") (pintype "bidirectional"))
    )
    (net (code "50") (name "SPI0_CE1_N") (class "Default")
      (node (ref "J8") (pin "1") (pinfunction "1_1") (pintype "passive"))
      (node (ref "X1") (pin "26") (pinfunction "P$26_26") (pintype "bidirectional"))
    )
    (net (code "51") (name "SPI0_MISO") (class "Default")
      (node (ref "J8") (pin "5") (pinfunction "5_5") (pintype "passive"))
      (node (ref "U$1") (pin "12-MISO/MQSL") (pinfunction "12-MISO/MQSL_12-MISO/MQSL") (pintype "bidirectional"))
      (node (ref "X1") (pin "21") (pinfunction "P$21_21") (pintype "bidirectional"))
    )
    (net (code "52") (name "SPI0_MOSI") (class "Default")
      (node (ref "J8") (pin "6") (pinfunction "6_6") (pintype "passive"))
      (node (ref "U$1") (pin "11-MOSI/CTX1") (pinfunction "11-MOSI/CTX1_11-MOSI/CTX1") (pintype "bidirectional"))
      (node (ref "X1") (pin "19") (pinfunction "P$19_19") (pintype "bidirectional"))
    )
    (net (code "53") (name "SPI0_SCLK") (class "Default")
      (node (ref "J8") (pin "4") (pinfunction "4_4") (pintype "passive"))
      (node (ref "U$1") (pin "13-SCK/LED") (pinfunction "13-SCK/LED_13-SCK/LED") (pintype "bidirectional"))
      (node (ref "X1") (pin "23") (pinfunction "P$23_23") (pintype "bidirectional"))
    )
    (net (code "54") (name "SPI1_CS1") (class "Default")
      (node (ref "U$1") (pin "38-A14/CS/IN1") (pinfunction "38-A14/CS/IN1_38-A14/CS/IN1") (pintype "bidirectional"))
      (node (ref "U3") (pin "5") (pinfunction "NSEL_5") (pintype "bidirectional"))
      (node (ref "U4") (pin "5") (pinfunction "NSS_5") (pintype "bidirectional"))
    )
    (net (code "55") (name "SPI1_D0") (class "Default")
      (node (ref "H1") (pin "2.2") (pinfunction "2.2_2.2") (pintype "bidirectional"))
      (node (ref "U$1") (pin "39-A15/CS/OUT1A") (pinfunction "39-A15/CS/OUT1A_39-A15/CS/OUT1A") (pintype "bidirectional"))
      (node (ref "U3") (pin "2") (pinfunction "SDO_2") (pintype "bidirectional"))
      (node (ref "U4") (pin "2") (pinfunction "MISO_2") (pintype "bidirectional"))
    )
    (net (code "56") (name "SPI1_D1") (class "Default")
      (node (ref "H1") (pin "2.3") (pinfunction "2.3_2.3") (pintype "bidirectional"))
      (node (ref "U$1") (pin "26-A12/MOSI1") (pinfunction "26-A12/MOSI1_26-A12/MOSI1") (pintype "bidirectional"))
      (node (ref "U3") (pin "3") (pinfunction "SDI_3") (pintype "bidirectional"))
      (node (ref "U4") (pin "3") (pinfunction "MOSI_3") (pintype "bidirectional"))
    )
    (net (code "57") (name "SPI1_SCLK") (class "Default")
      (node (ref "H1") (pin "2.1") (pinfunction "2.1_2.1") (pintype "bidirectional"))
      (node (ref "U$1") (pin "27-A13/SCK1") (pinfunction "27-A13/SCK1_27-A13/SCK1") (pintype "bidirectional"))
      (node (ref "U3") (pin "4") (pinfunction "SCK_4") (pintype "bidirectional"))
      (node (ref "U4") (pin "4") (pinfunction "SCK_4") (pintype "bidirectional"))
    )
    (net (code "58") (name "TX_ON") (class "Default")
      (node (ref "U$1") (pin "31-CTX3") (pinfunction "31-CTX3_31-CTX3") (pintype "bidirectional"))
      (node (ref "U3") (pin "11") (pinfunction "TXON_11") (pintype "bidirectional"))
    )
    (net (code "59") (name "T_CS") (class "Default")
      (node (ref "J4") (pin "1") (pinfunction "1_1") (pintype "passive"))
      (node (ref "U$1") (pin "10-CS\\MQSR") (pinfunction "10-CS/MQSR_10-CS\\MQSR") (pintype "bidirectional"))
    )
    (net (code "60") (name "T_CS1") (class "Default")
      (node (ref "H1") (pin "2.4") (pinfunction "2.4_2.4") (pintype "bidirectional"))
      (node (ref "U$1") (pin "9-OUT1C") (pinfunction "9-OUT1C_9-OUT1C") (pintype "bidirectional"))
    )
    (net (code "61") (name "T_GPIO2") (class "Default")
      (node (ref "J3") (pin "5") (pinfunction "5_5") (pintype "passive"))
      (node (ref "U$1") (pin "2-OUT2") (pinfunction "2-OUT2_2-OUT2") (pintype "bidirectional"))
    )
    (net (code "62") (name "T_GPIO3") (class "Default")
      (node (ref "J3") (pin "4") (pinfunction "4_4") (pintype "passive"))
      (node (ref "U$1") (pin "3-LRCLK2") (pinfunction "3-LRCLK2_3-LRCLK2") (pintype "bidirectional"))
    )
    (net (code "63") (name "T_GPIO4") (class "Default")
      (node (ref "J3") (pin "3") (pinfunction "3_3") (pintype "passive"))
      (node (ref "U$1") (pin "4-BCLK2") (pinfunction "4-BCLK2_4-BCLK2") (pintype "bidirectional"))
    )
    (net (code "64") (name "T_GPIO5") (class "Default")
      (node (ref "J3") (pin "2") (pinfunction "2_2") (pintype "passive"))
      (node (ref "U$1") (pin "5-IN2") (pinfunction "5-IN2_5-IN2") (pintype "bidirectional"))
    )
    (net (code "65") (name "T_GPIO6") (class "Default")
      (node (ref "J3") (pin "1") (pinfunction "1_1") (pintype "passive"))
      (node (ref "U$1") (pin "6-OUT1D") (pinfunction "6-OUT1D_6-OUT1D") (pintype "bidirectional"))
    )
    (net (code "66") (name "T_PROGRAM") (class "Default")
      (node (ref "J11") (pin "2") (pinfunction "2_2") (pintype "passive"))
      (node (ref "U$1") (pin "PROGRAM") (pinfunction "PROGRAM_PROGRAM") (pintype "bidirectional"))
    )
    (net (code "67") (name "T_VBAT") (class "Default")
      (node (ref "J11") (pin "1") (pinfunction "1_1") (pintype "passive"))
      (node (ref "U$1") (pin "VBAT") (pinfunction "VBAT_VBAT") (pintype "bidirectional"))
    )
    (net (code "68") (name "T_VUSB") (class "Default")
      (node (ref "J12") (pin "1") (pinfunction "1_1") (pintype "passive"))
      (node (ref "U$1") (pin "VUSB") (pinfunction "VUSB_VUSB") (pintype "bidirectional"))
    )
    (net (code "69") (name "UART2_RXD") (class "Default")
      (node (ref "J2") (pin "1") (pinfunction "1_1") (pintype "passive"))
      (node (ref "U$1") (pin "34-RX8") (pinfunction "34-RX8_34-RX8") (pintype "bidirectional"))
    )
    (net (code "70") (name "UART2_TXD") (class "Default")
      (node (ref "J2") (pin "3") (pinfunction "3_3") (pintype "passive"))
      (node (ref "U$1") (pin "35-TX8") (pinfunction "35/TX8_35-TX8") (pintype "bidirectional"))
    )
    (net (code "71") (name "UART4_RXD") (class "Default")
      (node (ref "H1") (pin "1.2") (pinfunction "1.2_1.2") (pintype "bidirectional"))
      (node (ref "U$1") (pin "0-RX1/CS1/CRX2") (pinfunction "0-RX1/CS1/CRX2_0-RX1/CS1/CRX2") (pintype "bidirectional"))
    )
    (net (code "72") (name "UART4_TXD") (class "Default")
      (node (ref "H1") (pin "1.1") (pinfunction "1.1_1.1") (pintype "bidirectional"))
      (node (ref "U$1") (pin "1-TX1/MISO1/CTX2") (pinfunction "1-TX1/MISO1/CTX2_1-TX1/MISO1/CTX2") (pintype "bidirectional"))
    )
    (net (code "73") (name "UART5_RXD") (class "Default")
      (node (ref "J14") (pin "3") (pinfunction "3_3") (pintype "passive"))
      (node (ref "U$1") (pin "29-TX7") (pinfunction "29-TX7_29-TX7") (pintype "bidirectional"))
      (node (ref "U6") (pin "42") (pinfunction "GPS_RXDO_42") (pintype "input"))
    )
    (net (code "74") (name "UART5_TXD") (class "Default")
      (node (ref "J14") (pin "4") (pinfunction "4_4") (pintype "passive"))
      (node (ref "U$1") (pin "28-RX7") (pinfunction "28-RX7_28-RX7") (pintype "bidirectional"))
      (node (ref "U6") (pin "44") (pinfunction "GPS_TXD0_44") (pintype "output"))
    )
    (net (code "75") (name "USB_DEV_D+") (class "Default")
      (node (ref "J12") (pin "4") (pinfunction "4_4") (pintype "passive"))
      (node (ref "U$1") (pin "D+") (pinfunction "D+_D+") (pintype "bidirectional"))
    )
    (net (code "76") (name "USB_DEV_D-") (class "Default")
      (node (ref "J12") (pin "3") (pinfunction "3_3") (pintype "passive"))
      (node (ref "U$1") (pin "D-") (pinfunction "D-_D-") (pintype "bidirectional"))
    )
    (net (code "77") (name "USB_HOST_D+") (class "Default")
      (node (ref "J13") (pin "1") (pinfunction "1_1") (pintype "passive"))
      (node (ref "U$1") (pin "DP") (pinfunction "DP_DP") (pintype "bidirectional"))
    )
    (net (code "78") (name "USB_HOST_D-") (class "Default")
      (node (ref "J13") (pin "2") (pinfunction "2_2") (pintype "passive"))
      (node (ref "U$1") (pin "DM") (pinfunction "DM_DM") (pintype "bidirectional"))
    )
    (net (code "79") (name "unconnected-(H1-Pad1.9)") (class "Default")
      (node (ref "H1") (pin "1.9") (pinfunction "1.9_1.9") (pintype "bidirectional"))
    )
    (net (code "80") (name "unconnected-(H1-Pad1.10)") (class "Default")
      (node (ref "H1") (pin "1.10") (pinfunction "1.10_1.10") (pintype "bidirectional"))
    )
    (net (code "81") (name "unconnected-(H1-Pad1.11)") (class "Default")
      (node (ref "H1") (pin "1.11") (pinfunction "1.11_1.11") (pintype "bidirectional"))
    )
    (net (code "82") (name "unconnected-(H1-Pad1.12)") (class "Default")
      (node (ref "H1") (pin "1.12") (pinfunction "1.12_1.12") (pintype "bidirectional"))
    )
    (net (code "83") (name "unconnected-(H1-Pad1.13)") (class "Default")
      (node (ref "H1") (pin "1.13") (pinfunction "1.13_1.13") (pintype "bidirectional"))
    )
    (net (code "84") (name "unconnected-(H1-Pad1.14)") (class "Default")
      (node (ref "H1") (pin "1.14") (pinfunction "1.14_1.14") (pintype "bidirectional"))
    )
    (net (code "85") (name "unconnected-(H1-Pad1.15)") (class "Default")
      (node (ref "H1") (pin "1.15") (pinfunction "1.15_1.15") (pintype "bidirectional"))
    )
    (net (code "86") (name "unconnected-(H1-Pad1.16)") (class "Default")
      (node (ref "H1") (pin "1.16") (pinfunction "1.16_1.16") (pintype "bidirectional"))
    )
    (net (code "87") (name "unconnected-(H1-Pad1.17)") (class "Default")
      (node (ref "H1") (pin "1.17") (pinfunction "1.17_1.17") (pintype "bidirectional"))
    )
    (net (code "88") (name "unconnected-(H1-Pad1.18)") (class "Default")
      (node (ref "H1") (pin "1.18") (pinfunction "1.18_1.18") (pintype "bidirectional"))
    )
    (net (code "89") (name "unconnected-(H1-Pad1.19)") (class "Default")
      (node (ref "H1") (pin "1.19") (pinfunction "1.19_1.19") (pintype "bidirectional"))
    )
    (net (code "90") (name "unconnected-(H1-Pad1.20)") (class "Default")
      (node (ref "H1") (pin "1.20") (pinfunction "1.20_1.20") (pintype "bidirectional"))
    )
    (net (code "91") (name "unconnected-(H1-Pad1.21)") (class "Default")
      (node (ref "H1") (pin "1.21") (pinfunction "1.21_1.21") (pintype "bidirectional"))
    )
    (net (code "92") (name "unconnected-(H1-Pad1.22)") (class "Default")
      (node (ref "H1") (pin "1.22") (pinfunction "1.22_1.22") (pintype "bidirectional"))
    )
    (net (code "93") (name "unconnected-(H1-Pad1.23)") (class "Default")
      (node (ref "H1") (pin "1.23") (pinfunction "1.23_1.23") (pintype "bidirectional"))
    )
    (net (code "94") (name "unconnected-(H1-Pad1.24)") (class "Default")
      (node (ref "H1") (pin "1.24") (pinfunction "1.24_1.24") (pintype "bidirectional"))
    )
    (net (code "95") (name "unconnected-(H1-Pad1.25)") (class "Default")
      (node (ref "H1") (pin "1.25") (pinfunction "1.25_1.25") (pintype "bidirectional"))
    )
    (net (code "96") (name "unconnected-(H1-Pad1.26)") (class "Default")
      (node (ref "H1") (pin "1.26") (pinfunction "1.26_1.26") (pintype "bidirectional"))
    )
    (net (code "97") (name "unconnected-(H1-Pad1.27)") (class "Default")
      (node (ref "H1") (pin "1.27") (pinfunction "1.27_1.27") (pintype "bidirectional"))
    )
    (net (code "98") (name "unconnected-(H1-Pad1.28)") (class "Default")
      (node (ref "H1") (pin "1.28") (pinfunction "1.28_1.28") (pintype "bidirectional"))
    )
    (net (code "99") (name "unconnected-(H1-Pad1.29)") (class "Default")
      (node (ref "H1") (pin "1.29") (pinfunction "1.29_1.29") (pintype "bidirectional"))
    )
    (net (code "100") (name "unconnected-(H1-Pad1.30)") (class "Default")
      (node (ref "H1") (pin "1.30") (pinfunction "1.30_1.30") (pintype "bidirectional"))
    )
    (net (code "101") (name "unconnected-(H1-Pad1.31)") (class "Default")
      (node (ref "H1") (pin "1.31") (pinfunction "1.31_1.31") (pintype "bidirectional"))
    )
    (net (code "102") (name "unconnected-(H1-Pad1.32)") (class "Default")
      (node (ref "H1") (pin "1.32") (pinfunction "1.32_1.32") (pintype "bidirectional"))
    )
    (net (code "103") (name "unconnected-(H1-Pad1.33)") (class "Default")
      (node (ref "H1") (pin "1.33") (pinfunction "1.33_1.33") (pintype "bidirectional"))
    )
    (net (code "104") (name "unconnected-(H1-Pad1.34)") (class "Default")
      (node (ref "H1") (pin "1.34") (pinfunction "1.34_1.34") (pintype "bidirectional"))
    )
    (net (code "105") (name "unconnected-(H1-Pad1.35)") (class "Default")
      (node (ref "H1") (pin "1.35") (pinfunction "1.35_1.35") (pintype "bidirectional"))
    )
    (net (code "106") (name "unconnected-(H1-Pad1.36)") (class "Default")
      (node (ref "H1") (pin "1.36") (pinfunction "1.36_1.36") (pintype "bidirectional"))
    )
    (net (code "107") (name "unconnected-(H1-Pad1.37)") (class "Default")
      (node (ref "H1") (pin "1.37") (pinfunction "1.37_1.37") (pintype "bidirectional"))
    )
    (net (code "108") (name "unconnected-(H1-Pad1.38)") (class "Default")
      (node (ref "H1") (pin "1.38") (pinfunction "1.38_1.38") (pintype "bidirectional"))
    )
    (net (code "109") (name "unconnected-(H1-Pad1.39)") (class "Default")
      (node (ref "H1") (pin "1.39") (pinfunction "1.39_1.39") (pintype "bidirectional"))
    )
    (net (code "110") (name "unconnected-(H1-Pad1.40)") (class "Default")
      (node (ref "H1") (pin "1.40") (pinfunction "1.40_1.40") (pintype "bidirectional"))
    )
    (net (code "111") (name "unconnected-(H1-Pad1.42)") (class "Default")
      (node (ref "H1") (pin "1.42") (pinfunction "1.42_1.42") (pintype "bidirectional"))
    )
    (net (code "112") (name "unconnected-(H1-Pad1.44)") (class "Default")
      (node (ref "H1") (pin "1.44") (pinfunction "1.44_1.44") (pintype "bidirectional"))
    )
    (net (code "113") (name "unconnected-(H1-Pad1.45)") (class "Default")
      (node (ref "H1") (pin "1.45") (pinfunction "1.45_1.45") (pintype "bidirectional"))
    )
    (net (code "114") (name "unconnected-(H1-Pad1.46)") (class "Default")
      (node (ref "H1") (pin "1.46") (pinfunction "1.46_1.46") (pintype "bidirectional"))
    )
    (net (code "115") (name "unconnected-(H1-Pad1.47)") (class "Default")
      (node (ref "H1") (pin "1.47") (pinfunction "1.47_1.47") (pintype "bidirectional"))
    )
    (net (code "116") (name "unconnected-(H1-Pad1.48)") (class "Default")
      (node (ref "H1") (pin "1.48") (pinfunction "1.48_1.48") (pintype "bidirectional"))
    )
    (net (code "117") (name "unconnected-(H1-Pad1.49)") (class "Default")
      (node (ref "H1") (pin "1.49") (pinfunction "1.49_1.49") (pintype "bidirectional"))
    )
    (net (code "118") (name "unconnected-(H1-Pad1.50)") (class "Default")
      (node (ref "H1") (pin "1.50") (pinfunction "1.50_1.50") (pintype "bidirectional"))
    )
    (net (code "119") (name "unconnected-(H1-Pad1.51)") (class "Default")
      (node (ref "H1") (pin "1.51") (pinfunction "1.51_1.51") (pintype "bidirectional"))
    )
    (net (code "120") (name "unconnected-(H1-Pad1.52)") (class "Default")
      (node (ref "H1") (pin "1.52") (pinfunction "1.52_1.52") (pintype "bidirectional"))
    )
    (net (code "121") (name "unconnected-(H1-Pad2.5)") (class "Default")
      (node (ref "H1") (pin "2.5") (pinfunction "2.5_2.5") (pintype "bidirectional"))
    )
    (net (code "122") (name "unconnected-(H1-Pad2.6)") (class "Default")
      (node (ref "H1") (pin "2.6") (pinfunction "2.6_2.6") (pintype "bidirectional"))
    )
    (net (code "123") (name "unconnected-(H1-Pad2.8)") (class "Default")
      (node (ref "H1") (pin "2.8") (pinfunction "2.8_2.8") (pintype "bidirectional"))
    )
    (net (code "124") (name "unconnected-(H1-Pad2.9)") (class "Default")
      (node (ref "H1") (pin "2.9") (pinfunction "2.9_2.9") (pintype "bidirectional"))
    )
    (net (code "125") (name "unconnected-(H1-Pad2.10)") (class "Default")
      (node (ref "H1") (pin "2.10") (pinfunction "2.10_2.10") (pintype "bidirectional"))
    )
    (net (code "126") (name "unconnected-(H1-Pad2.11)") (class "Default")
      (node (ref "H1") (pin "2.11") (pinfunction "2.11_2.11") (pintype "bidirectional"))
    )
    (net (code "127") (name "unconnected-(H1-Pad2.12)") (class "Default")
      (node (ref "H1") (pin "2.12") (pinfunction "2.12_2.12") (pintype "bidirectional"))
    )
    (net (code "128") (name "unconnected-(H1-Pad2.13)") (class "Default")
      (node (ref "H1") (pin "2.13") (pinfunction "2.13_2.13") (pintype "bidirectional"))
    )
    (net (code "129") (name "unconnected-(H1-Pad2.15)") (class "Default")
      (node (ref "H1") (pin "2.15") (pinfunction "2.15_2.15") (pintype "bidirectional"))
    )
    (net (code "130") (name "unconnected-(H1-Pad2.16)") (class "Default")
      (node (ref "H1") (pin "2.16") (pinfunction "2.16_2.16") (pintype "bidirectional"))
    )
    (net (code "131") (name "unconnected-(H1-Pad2.18)") (class "Default")
      (node (ref "H1") (pin "2.18") (pinfunction "2.18_2.18") (pintype "bidirectional"))
    )
    (net (code "132") (name "unconnected-(H1-Pad2.19)") (class "Default")
      (node (ref "H1") (pin "2.19") (pinfunction "2.19_2.19") (pintype "bidirectional"))
    )
    (net (code "133") (name "unconnected-(H1-Pad2.20)") (class "Default")
      (node (ref "H1") (pin "2.20") (pinfunction "2.20_2.20") (pintype "bidirectional"))
    )
    (net (code "134") (name "unconnected-(H1-Pad2.23)") (class "Default")
      (node (ref "H1") (pin "2.23") (pinfunction "2.23_2.23") (pintype "bidirectional"))
    )
    (net (code "135") (name "unconnected-(H1-Pad2.24)") (class "Default")
      (node (ref "H1") (pin "2.24") (pinfunction "2.24_2.24") (pintype "bidirectional"))
    )
    (net (code "136") (name "unconnected-(H1-Pad2.31)") (class "Default")
      (node (ref "H1") (pin "2.31") (pinfunction "2.31_2.31") (pintype "bidirectional"))
    )
    (net (code "137") (name "unconnected-(H1-Pad2.33)") (class "Default")
      (node (ref "H1") (pin "2.33") (pinfunction "2.33_2.33") (pintype "bidirectional"))
    )
    (net (code "138") (name "unconnected-(H1-Pad2.34)") (class "Default")
      (node (ref "H1") (pin "2.34") (pinfunction "2.34_2.34") (pintype "bidirectional"))
    )
    (net (code "139") (name "unconnected-(H1-Pad2.35)") (class "Default")
      (node (ref "H1") (pin "2.35") (pinfunction "2.35_2.35") (pintype "bidirectional"))
    )
    (net (code "140") (name "unconnected-(H1-Pad2.36)") (class "Default")
      (node (ref "H1") (pin "2.36") (pinfunction "2.36_2.36") (pintype "bidirectional"))
    )
    (net (code "141") (name "unconnected-(H1-Pad2.37)") (class "Default")
      (node (ref "H1") (pin "2.37") (pinfunction "2.37_2.37") (pintype "bidirectional"))
    )
    (net (code "142") (name "unconnected-(H1-Pad2.38)") (class "Default")
      (node (ref "H1") (pin "2.38") (pinfunction "2.38_2.38") (pintype "bidirectional"))
    )
    (net (code "143") (name "unconnected-(H1-Pad2.39)") (class "Default")
      (node (ref "H1") (pin "2.39") (pinfunction "2.39_2.39") (pintype "bidirectional"))
    )
    (net (code "144") (name "unconnected-(H1-Pad2.40)") (class "Default")
      (node (ref "H1") (pin "2.40") (pinfunction "2.40_2.40") (pintype "bidirectional"))
    )
    (net (code "145") (name "unconnected-(H1-Pad2.41)") (class "Default")
      (node (ref "H1") (pin "2.41") (pinfunction "2.41_2.41") (pintype "bidirectional"))
    )
    (net (code "146") (name "unconnected-(H1-Pad2.42)") (class "Default")
      (node (ref "H1") (pin "2.42") (pinfunction "2.42_2.42") (pintype "bidirectional"))
    )
    (net (code "147") (name "unconnected-(H1-Pad2.43)") (class "Default")
      (node (ref "H1") (pin "2.43") (pinfunction "2.43_2.43") (pintype "bidirectional"))
    )
    (net (code "148") (name "unconnected-(H1-Pad2.44)") (class "Default")
      (node (ref "H1") (pin "2.44") (pinfunction "2.44_2.44") (pintype "bidirectional"))
    )
    (net (code "149") (name "unconnected-(H1-Pad2.45)") (class "Default")
      (node (ref "H1") (pin "2.45") (pinfunction "2.45_2.45") (pintype "bidirectional"))
    )
    (net (code "150") (name "unconnected-(H1-Pad2.46)") (class "Default")
      (node (ref "H1") (pin "2.46") (pinfunction "2.46_2.46") (pintype "bidirectional"))
    )
    (net (code "151") (name "unconnected-(H1-Pad2.49)") (class "Default")
      (node (ref "H1") (pin "2.49") (pinfunction "2.49_2.49") (pintype "bidirectional"))
    )
    (net (code "152") (name "unconnected-(H1-Pad2.50)") (class "Default")
      (node (ref "H1") (pin "2.50") (pinfunction "2.50_2.50") (pintype "bidirectional"))
    )
    (net (code "153") (name "unconnected-(H1-Pad2.51)") (class "Default")
      (node (ref "H1") (pin "2.51") (pinfunction "2.51_2.51") (pintype "bidirectional"))
    )
    (net (code "154") (name "unconnected-(H1-Pad2.52)") (class "Default")
      (node (ref "H1") (pin "2.52") (pinfunction "2.52_2.52") (pintype "bidirectional"))
    )
    (net (code "155") (name "unconnected-(H1-PadP$1)") (class "Default")
      (node (ref "H1") (pin "P$1") (pinfunction "P$1_P$1") (pintype "bidirectional"))
    )
    (net (code "156") (name "unconnected-(H1-PadP$2)") (class "Default")
      (node (ref "H1") (pin "P$2") (pinfunction "P$2_P$2") (pintype "bidirectional"))
    )
    (net (code "157") (name "unconnected-(H1-PadP$3)") (class "Default")
      (node (ref "H1") (pin "P$3") (pinfunction "P$3_P$3") (pintype "bidirectional"))
    )
    (net (code "158") (name "unconnected-(U$1-Pad40-A16{slash}CS1)") (class "Default")
      (node (ref "U$1") (pin "40-A16/CS1") (pinfunction "40-A16/CS1_40-A16/CS1") (pintype "bidirectional"))
    )
    (net (code "159") (name "unconnected-(U$1-PadON{slash}OFF)") (class "Default")
      (node (ref "U$1") (pin "ON/OFF") (pinfunction "ON/OFF_ON/OFF") (pintype "bidirectional"))
    )
    (net (code "160") (name "unconnected-(U1-NC-Pad7)") (class "Default")
      (node (ref "U1") (pin "7") (pinfunction "NC_7") (pintype "no_connect"))
    )
    (net (code "161") (name "unconnected-(U1-NC_2-Pad2)") (class "Default")
      (node (ref "U1") (pin "2") (pinfunction "NC_2_2") (pintype "no_connect"))
    )
    (net (code "162") (name "unconnected-(U1-NC_3-Pad3)") (class "Default")
      (node (ref "U1") (pin "3") (pinfunction "NC_3_3") (pintype "no_connect"))
    )
    (net (code "163") (name "unconnected-(U1-NC_4-Pad6)") (class "Default")
      (node (ref "U1") (pin "6") (pinfunction "NC_4_6") (pintype "no_connect"))
    )
    (net (code "164") (name "unconnected-(U3-GPIO_2-Pad16)") (class "Default")
      (node (ref "U3") (pin "16") (pinfunction "GPIO_2_16") (pintype "bidirectional"))
    )
    (net (code "165") (name "unconnected-(U4-DIO0-Pad14)") (class "Default")
      (node (ref "U4") (pin "14") (pinfunction "DIO0_14") (pintype "bidirectional"))
    )
    (net (code "166") (name "unconnected-(U4-DIO2-Pad16)") (class "Default")
      (node (ref "U4") (pin "16") (pinfunction "DIO2_16") (pintype "bidirectional"))
    )
    (net (code "167") (name "unconnected-(U4-DIO3-Pad11)") (class "Default")
      (node (ref "U4") (pin "11") (pinfunction "DIO3_11") (pintype "bidirectional"))
    )
    (net (code "168") (name "unconnected-(U4-DIO4-Pad12)") (class "Default")
      (node (ref "U4") (pin "12") (pinfunction "DIO4_12") (pintype "bidirectional"))
    )
    (net (code "169") (name "unconnected-(U4-DIO5-Pad7)") (class "Default")
      (node (ref "U4") (pin "7") (pinfunction "DIO5_7") (pintype "bidirectional"))
    )
    (net (code "170") (name "unconnected-(U5-Pad1)") (class "Default")
      (node (ref "U5") (pin "1") (pinfunction "1_1") (pintype "passive"))
    )
    (net (code "171") (name "unconnected-(U6-P$3-Pad3)") (class "Default")
      (node (ref "U6") (pin "3") (pinfunction "P$3_3") (pintype "bidirectional"))
    )
    (net (code "172") (name "unconnected-(U6-P$4-Pad4)") (class "Default")
      (node (ref "U6") (pin "4") (pinfunction "P$4_4") (pintype "bidirectional"))
    )
    (net (code "173") (name "unconnected-(U6-P$5-Pad5)") (class "Default")
      (node (ref "U6") (pin "5") (pinfunction "P$5_5") (pintype "bidirectional"))
    )
    (net (code "174") (name "unconnected-(U6-P$6-Pad6)") (class "Default")
      (node (ref "U6") (pin "6") (pinfunction "P$6_6") (pintype "bidirectional"))
    )
    (net (code "175") (name "unconnected-(U6-P$8-Pad8)") (class "Default")
      (node (ref "U6") (pin "8") (pinfunction "P$8_8") (pintype "bidirectional"))
    )
    (net (code "176") (name "unconnected-(U6-P$12-Pad12)") (class "Default")
      (node (ref "U6") (pin "12") (pinfunction "P$12_12") (pintype "bidirectional"))
    )
    (net (code "177") (name "unconnected-(U6-P$13-Pad13)") (class "Default")
      (node (ref "U6") (pin "13") (pinfunction "P$13_13") (pintype "bidirectional"))
    )
    (net (code "178") (name "unconnected-(U6-P$14-Pad14)") (class "Default")
      (node (ref "U6") (pin "14") (pinfunction "P$14_14") (pintype "bidirectional"))
    )
    (net (code "179") (name "unconnected-(U6-P$16-Pad16)") (class "Default")
      (node (ref "U6") (pin "16") (pinfunction "P$16_16") (pintype "bidirectional"))
    )
    (net (code "180") (name "unconnected-(U6-P$17-Pad17)") (class "Default")
      (node (ref "U6") (pin "17") (pinfunction "P$17_17") (pintype "bidirectional"))
    )
    (net (code "181") (name "unconnected-(U6-P$20-Pad20)") (class "Default")
      (node (ref "U6") (pin "20") (pinfunction "P$20_20") (pintype "bidirectional"))
    )
    (net (code "182") (name "unconnected-(U6-P$23-Pad23)") (class "Default")
      (node (ref "U6") (pin "23") (pinfunction "P$23_23") (pintype "bidirectional"))
    )
    (net (code "183") (name "unconnected-(U6-P$26-Pad26)") (class "Default")
      (node (ref "U6") (pin "26") (pinfunction "P$26_26") (pintype "bidirectional"))
    )
    (net (code "184") (name "unconnected-(U6-P$30-Pad30)") (class "Default")
      (node (ref "U6") (pin "30") (pinfunction "P$30_30") (pintype "bidirectional"))
    )
    (net (code "185") (name "unconnected-(U6-P$34-Pad34)") (class "Default")
      (node (ref "U6") (pin "34") (pinfunction "P$34_34") (pintype "bidirectional"))
    )
    (net (code "186") (name "unconnected-(U6-P$35-Pad35)") (class "Default")
      (node (ref "U6") (pin "35") (pinfunction "P$35_35") (pintype "bidirectional"))
    )
    (net (code "187") (name "unconnected-(U6-P$36-Pad36)") (class "Default")
      (node (ref "U6") (pin "36") (pinfunction "P$36_36") (pintype "bidirectional"))
    )
    (net (code "188") (name "unconnected-(U6-P$37-Pad37)") (class "Default")
      (node (ref "U6") (pin "37") (pinfunction "P$37_37") (pintype "bidirectional"))
    )
    (net (code "189") (name "unconnected-(U6-P$38-Pad38)") (class "Default")
      (node (ref "U6") (pin "38") (pinfunction "P$38_38") (pintype "bidirectional"))
    )
    (net (code "190") (name "unconnected-(U6-P$39-Pad39)") (class "Default")
      (node (ref "U6") (pin "39") (pinfunction "P$39_39") (pintype "bidirectional"))
    )
    (net (code "191") (name "unconnected-(U6-P$40-Pad40)") (class "Default")
      (node (ref "U6") (pin "40") (pinfunction "P$40_40") (pintype "bidirectional"))
    )
    (net (code "192") (name "unconnected-(U6-P$41-Pad41)") (class "Default")
      (node (ref "U6") (pin "41") (pinfunction "P$41_41") (pintype "bidirectional"))
    )
    (net (code "193") (name "unconnected-(U6-P$43-Pad43)") (class "Default")
      (node (ref "U6") (pin "43") (pinfunction "P$43_43") (pintype "bidirectional"))
    )
    (net (code "194") (name "unconnected-(U6-P$45-Pad45)") (class "Default")
      (node (ref "U6") (pin "45") (pinfunction "P$45_45") (pintype "bidirectional"))
    )
    (net (code "195") (name "unconnected-(U6-P$46-Pad46)") (class "Default")
      (node (ref "U6") (pin "46") (pinfunction "P$46_46") (pintype "bidirectional"))
    )
    (net (code "196") (name "unconnected-(U6-P$47-Pad47)") (class "Default")
      (node (ref "U6") (pin "47") (pinfunction "P$47_47") (pintype "bidirectional"))
    )
    (net (code "197") (name "unconnected-(U6-P$48-Pad48)") (class "Default")
      (node (ref "U6") (pin "48") (pinfunction "P$48_48") (pintype "bidirectional"))
    )
    (net (code "198") (name "unconnected-(U6-P$49-Pad49)") (class "Default")
      (node (ref "U6") (pin "49") (pinfunction "P$49_49") (pintype "bidirectional"))
    )
    (net (code "199") (name "unconnected-(U6-P$50-Pad50)") (class "Default")
      (node (ref "U6") (pin "50") (pinfunction "P$50_50") (pintype "bidirectional"))
    )
    (net (code "200") (name "unconnected-(U6-P$51-Pad51)") (class "Default")
      (node (ref "U6") (pin "51") (pinfunction "P$51_51") (pintype "bidirectional"))
    )
    (net (code "201") (name "unconnected-(U6-P$52-Pad52)") (class "Default")
      (node (ref "U6") (pin "52") (pinfunction "P$52_52") (pintype "bidirectional"))
    )
    (net (code "202") (name "unconnected-(U6-P$53-Pad53)") (class "Default")
      (node (ref "U6") (pin "53") (pinfunction "P$53_53") (pintype "bidirectional"))
    )
    (net (code "203") (name "unconnected-(U6-P$54-Pad54)") (class "Default")
      (node (ref "U6") (pin "54") (pinfunction "P$54_54") (pintype "bidirectional"))
    )
    (net (code "204") (name "unconnected-(U6-P$55-Pad55)") (class "Default")
      (node (ref "U6") (pin "55") (pinfunction "P$55_55") (pintype "bidirectional"))
    )
    (net (code "205") (name "unconnected-(U6-P$56-Pad56)") (class "Default")
      (node (ref "U6") (pin "56") (pinfunction "P$56_56") (pintype "bidirectional"))
    )
    (net (code "206") (name "unconnected-(U6-P$57-Pad57)") (class "Default")
      (node (ref "U6") (pin "57") (pinfunction "P$57_57") (pintype "bidirectional"))
    )
    (net (code "207") (name "unconnected-(U6-P$59-Pad59)") (class "Default")
      (node (ref "U6") (pin "59") (pinfunction "P$59_59") (pintype "bidirectional"))
    )
    (net (code "208") (name "unconnected-(U6-P$60-Pad60)") (class "Default")
      (node (ref "U6") (pin "60") (pinfunction "P$60_60") (pintype "bidirectional"))
    )
    (net (code "209") (name "unconnected-(U6-P$61-Pad61)") (class "Default")
      (node (ref "U6") (pin "61") (pinfunction "P$61_61") (pintype "bidirectional"))
    )
    (net (code "210") (name "unconnected-(U6-P$62-Pad62)") (class "Default")
      (node (ref "U6") (pin "62") (pinfunction "P$62_62") (pintype "bidirectional"))
    )
    (net (code "211") (name "unconnected-(U6-P$63-Pad63)") (class "Default")
      (node (ref "U6") (pin "63") (pinfunction "P$63_63") (pintype "bidirectional"))
    )
    (net (code "212") (name "unconnected-(U6-P$65-Pad65)") (class "Default")
      (node (ref "U6") (pin "65") (pinfunction "P$65_65") (pintype "bidirectional"))
    )
    (net (code "213") (name "unconnected-(U6-P$66-Pad66)") (class "Default")
      (node (ref "U6") (pin "66") (pinfunction "P$66_66") (pintype "bidirectional"))
    )
    (net (code "214") (name "unconnected-(U6-P$67-Pad67)") (class "Default")
      (node (ref "U6") (pin "67") (pinfunction "P$67_67") (pintype "bidirectional"))
    )
    (net (code "215") (name "unconnected-(U6-P$68-Pad68)") (class "Default")
      (node (ref "U6") (pin "68") (pinfunction "P$68_68") (pintype "bidirectional"))
    )
    (net (code "216") (name "unconnected-(U6-P$69-Pad69)") (class "Default")
      (node (ref "U6") (pin "69") (pinfunction "P$69_69") (pintype "bidirectional"))
    )
    (net (code "217") (name "unconnected-(X1-P$1-Pad1)") (class "Default")
      (node (ref "X1") (pin "1") (pinfunction "P$1_1") (pintype "bidirectional"))
    )
    (net (code "218") (name "unconnected-(X1-P$4-Pad4)") (class "Default")
      (node (ref "X1") (pin "4") (pinfunction "P$4_4") (pintype "bidirectional"))
    )
    (net (code "219") (name "unconnected-(X1-P$6-Pad6)") (class "Default")
      (node (ref "X1") (pin "6") (pinfunction "P$6_6") (pintype "bidirectional"))
    )
    (net (code "220") (name "unconnected-(X1-P$7-Pad7)") (class "Default")
      (node (ref "X1") (pin "7") (pinfunction "P$7_7") (pintype "bidirectional"))
    )
    (net (code "221") (name "unconnected-(X1-P$9-Pad9)") (class "Default")
      (node (ref "X1") (pin "9") (pinfunction "P$9_9") (pintype "bidirectional"))
    )
    (net (code "222") (name "unconnected-(X1-P$10-Pad10)") (class "Default")
      (node (ref "X1") (pin "10") (pinfunction "P$10_10") (pintype "bidirectional"))
    )
    (net (code "223") (name "unconnected-(X1-P$12-Pad12)") (class "Default")
      (node (ref "X1") (pin "12") (pinfunction "P$12_12") (pintype "bidirectional"))
    )
    (net (code "224") (name "unconnected-(X1-P$14-Pad14)") (class "Default")
      (node (ref "X1") (pin "14") (pinfunction "P$14_14") (pintype "bidirectional"))
    )
    (net (code "225") (name "unconnected-(X1-P$17-Pad17)") (class "Default")
      (node (ref "X1") (pin "17") (pinfunction "P$17_17") (pintype "bidirectional"))
    )
    (net (code "226") (name "unconnected-(X1-P$20-Pad20)") (class "Default")
      (node (ref "X1") (pin "20") (pinfunction "P$20_20") (pintype "bidirectional"))
    )
    (net (code "227") (name "unconnected-(X1-P$25-Pad25)") (class "Default")
      (node (ref "X1") (pin "25") (pinfunction "P$25_25") (pintype "bidirectional"))
    )
    (net (code "228") (name "unconnected-(X1-P$27-Pad27)") (class "Default")
      (node (ref "X1") (pin "27") (pinfunction "P$27_27") (pintype "bidirectional"))
    )
    (net (code "229") (name "unconnected-(X1-P$28-Pad28)") (class "Default")
      (node (ref "X1") (pin "28") (pinfunction "P$28_28") (pintype "bidirectional"))
    )
    (net (code "230") (name "unconnected-(X1-P$29-Pad29)") (class "Default")
      (node (ref "X1") (pin "29") (pinfunction "P$29_29") (pintype "bidirectional"))
    )
    (net (code "231") (name "unconnected-(X1-P$30-Pad30)") (class "Default")
      (node (ref "X1") (pin "30") (pinfunction "P$30_30") (pintype "bidirectional"))
    )
    (net (code "232") (name "unconnected-(X1-P$31-Pad31)") (class "Default")
      (node (ref "X1") (pin "31") (pinfunction "P$31_31") (pintype "bidirectional"))
    )
    (net (code "233") (name "unconnected-(X1-P$32-Pad32)") (class "Default")
      (node (ref "X1") (pin "32") (pinfunction "P$32_32") (pintype "bidirectional"))
    )
    (net (code "234") (name "unconnected-(X1-P$33-Pad33)") (class "Default")
      (node (ref "X1") (pin "33") (pinfunction "P$33_33") (pintype "bidirectional"))
    )
    (net (code "235") (name "unconnected-(X1-P$34-Pad34)") (class "Default")
      (node (ref "X1") (pin "34") (pinfunction "P$34_34") (pintype "bidirectional"))
    )
    (net (code "236") (name "unconnected-(X1-P$35-Pad35)") (class "Default")
      (node (ref "X1") (pin "35") (pinfunction "P$35_35") (pintype "bidirectional"))
    )
    (net (code "237") (name "unconnected-(X1-P$36-Pad36)") (class "Default")
      (node (ref "X1") (pin "36") (pinfunction "P$36_36") (pintype "bidirectional"))
    )
    (net (code "238") (name "unconnected-(X1-P$37-Pad37)") (class "Default")
      (node (ref "X1") (pin "37") (pinfunction "P$37_37") (pintype "bidirectional"))
    )
    (net (code "239") (name "unconnected-(X1-P$38-Pad38)") (class "Default")
      (node (ref "X1") (pin "38") (pinfunction "P$38_38") (pintype "bidirectional"))
    )
    (net (code "240") (name "unconnected-(X1-P$40-Pad40)") (class "Default")
      (node (ref "X1") (pin "40") (pinfunction "P$40_40") (pintype "bidirectional"))
    )
    (net (code "241") (name "unconnected-(X2-Pad1)") (class "Default")
      (node (ref "X2") (pin "1") (pinfunction "1_1") (pintype "passive"))
    )
    (net (code "242") (name "unconnected-(X2AA-1-Pad33)") (class "Default")
      (node (ref "X2") (pin "33") (pinfunction "1_33") (pintype "passive"))
    )
    (net (code "243") (name "unconnected-(X2AB-1-Pad34)") (class "Default")
      (node (ref "X2") (pin "34") (pinfunction "1_34") (pintype "passive"))
    )
    (net (code "244") (name "unconnected-(X2AC-1-Pad35)") (class "Default")
      (node (ref "X2") (pin "35") (pinfunction "1_35") (pintype "passive"))
    )
    (net (code "245") (name "unconnected-(X2AD-1-Pad36)") (class "Default")
      (node (ref "X2") (pin "36") (pinfunction "1_36") (pintype "passive"))
    )
    (net (code "246") (name "unconnected-(X2AE-1-Pad37)") (class "Default")
      (node (ref "X2") (pin "37") (pinfunction "1_37") (pintype "passive"))
    )
    (net (code "247") (name "unconnected-(X2AF-1-Pad38)") (class "Default")
      (node (ref "X2") (pin "38") (pinfunction "1_38") (pintype "passive"))
    )
    (net (code "248") (name "unconnected-(X2AG-1-Pad39)") (class "Default")
      (node (ref "X2") (pin "39") (pinfunction "1_39") (pintype "passive"))
    )
    (net (code "249") (name "unconnected-(X2AH-1-Pad4)") (class "Default")
      (node (ref "X2") (pin "4") (pinfunction "1_4") (pintype "passive"))
    )
    (net (code "250") (name "unconnected-(X2AI-1-Pad40)") (class "Default")
      (node (ref "X2") (pin "40") (pinfunction "1_40") (pintype "passive"))
    )
    (net (code "251") (name "unconnected-(X2AJ-1-Pad5)") (class "Default")
      (node (ref "X2") (pin "5") (pinfunction "1_5") (pintype "passive"))
    )
    (net (code "252") (name "unconnected-(X2AK-1-Pad6)") (class "Default")
      (node (ref "X2") (pin "6") (pinfunction "1_6") (pintype "passive"))
    )
    (net (code "253") (name "unconnected-(X2AL-1-Pad7)") (class "Default")
      (node (ref "X2") (pin "7") (pinfunction "1_7") (pintype "passive"))
    )
    (net (code "254") (name "unconnected-(X2AM-1-Pad8)") (class "Default")
      (node (ref "X2") (pin "8") (pinfunction "1_8") (pintype "passive"))
    )
    (net (code "255") (name "unconnected-(X2AN-1-Pad9)") (class "Default")
      (node (ref "X2") (pin "9") (pinfunction "1_9") (pintype "passive"))
    )
    (net (code "256") (name "unconnected-(X2B-1-Pad10)") (class "Default")
      (node (ref "X2") (pin "10") (pinfunction "1_10") (pintype "passive"))
    )
    (net (code "257") (name "unconnected-(X2C-1-Pad11)") (class "Default")
      (node (ref "X2") (pin "11") (pinfunction "1_11") (pintype "passive"))
    )
    (net (code "258") (name "unconnected-(X2D-1-Pad12)") (class "Default")
      (node (ref "X2") (pin "12") (pinfunction "1_12") (pintype "passive"))
    )
    (net (code "259") (name "unconnected-(X2E-1-Pad13)") (class "Default")
      (node (ref "X2") (pin "13") (pinfunction "1_13") (pintype "passive"))
    )
    (net (code "260") (name "unconnected-(X2F-1-Pad14)") (class "Default")
      (node (ref "X2") (pin "14") (pinfunction "1_14") (pintype "passive"))
    )
    (net (code "261") (name "unconnected-(X2G-1-Pad15)") (class "Default")
      (node (ref "X2") (pin "15") (pinfunction "1_15") (pintype "passive"))
    )
    (net (code "262") (name "unconnected-(X2H-1-Pad16)") (class "Default")
      (node (ref "X2") (pin "16") (pinfunction "1_16") (pintype "passive"))
    )
    (net (code "263") (name "unconnected-(X2I-1-Pad17)") (class "Default")
      (node (ref "X2") (pin "17") (pinfunction "1_17") (pintype "passive"))
    )
    (net (code "264") (name "unconnected-(X2J-1-Pad18)") (class "Default")
      (node (ref "X2") (pin "18") (pinfunction "1_18") (pintype "passive"))
    )
    (net (code "265") (name "unconnected-(X2K-1-Pad19)") (class "Default")
      (node (ref "X2") (pin "19") (pinfunction "1_19") (pintype "passive"))
    )
    (net (code "266") (name "unconnected-(X2L-1-Pad2)") (class "Default")
      (node (ref "X2") (pin "2") (pinfunction "1_2") (pintype "passive"))
    )
    (net (code "267") (name "unconnected-(X2M-1-Pad20)") (class "Default")
      (node (ref "X2") (pin "20") (pinfunction "1_20") (pintype "passive"))
    )
    (net (code "268") (name "unconnected-(X2N-1-Pad21)") (class "Default")
      (node (ref "X2") (pin "21") (pinfunction "1_21") (pintype "passive"))
    )
    (net (code "269") (name "unconnected-(X2O-1-Pad22)") (class "Default")
      (node (ref "X2") (pin "22") (pinfunction "1_22") (pintype "passive"))
    )
    (net (code "270") (name "unconnected-(X2P-1-Pad23)") (class "Default")
      (node (ref "X2") (pin "23") (pinfunction "1_23") (pintype "passive"))
    )
    (net (code "271") (name "unconnected-(X2Q-1-Pad24)") (class "Default")
      (node (ref "X2") (pin "24") (pinfunction "1_24") (pintype "passive"))
    )
    (net (code "272") (name "unconnected-(X2R-1-Pad25)") (class "Default")
      (node (ref "X2") (pin "25") (pinfunction "1_25") (pintype "passive"))
    )
    (net (code "273") (name "unconnected-(X2S-1-Pad26)") (class "Default")
      (node (ref "X2") (pin "26") (pinfunction "1_26") (pintype "passive"))
    )
    (net (code "274") (name "unconnected-(X2T-1-Pad27)") (class "Default")
      (node (ref "X2") (pin "27") (pinfunction "1_27") (pintype "passive"))
    )
    (net (code "275") (name "unconnected-(X2U-1-Pad28)") (class "Default")
      (node (ref "X2") (pin "28") (pinfunction "1_28") (pintype "passive"))
    )
    (net (code "276") (name "unconnected-(X2V-1-Pad29)") (class "Default")
      (node (ref "X2") (pin "29") (pinfunction "1_29") (pintype "passive"))
    )
    (net (code "277") (name "unconnected-(X2W-1-Pad3)") (class "Default")
      (node (ref "X2") (pin "3") (pinfunction "1_3") (pintype "passive"))
    )
    (net (code "278") (name "unconnected-(X2X-1-Pad30)") (class "Default")
      (node (ref "X2") (pin "30") (pinfunction "1_30") (pintype "passive"))
    )
    (net (code "279") (name "unconnected-(X2Y-1-Pad31)") (class "Default")
      (node (ref "X2") (pin "31") (pinfunction "1_31") (pintype "passive"))
    )
    (net (code "280") (name "unconnected-(X2Z-1-Pad32)") (class "Default")
      (node (ref "X2") (pin "32") (pinfunction "1_32") (pintype "passive"))
    )
  )
)
